# -1-_-01-00-001.net
KiCad netlist of a schematic drawn in Altium Designer
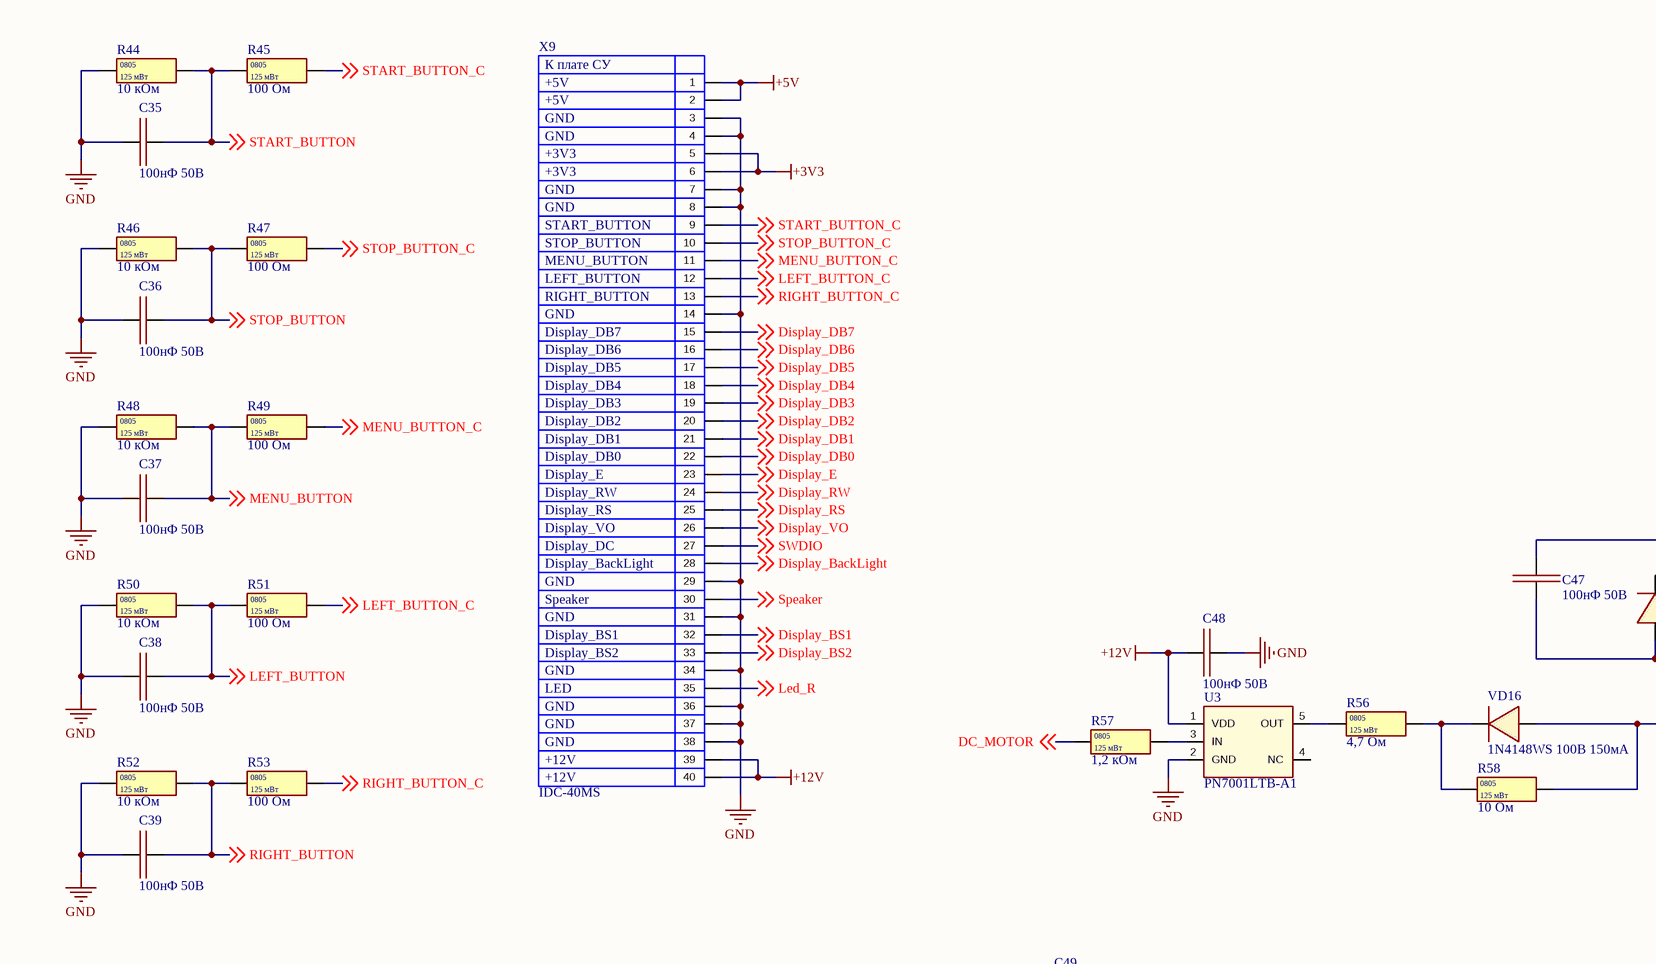
[diagram p0: СТЖ-1-ПУ-01-00-001.SchDoc, top left]
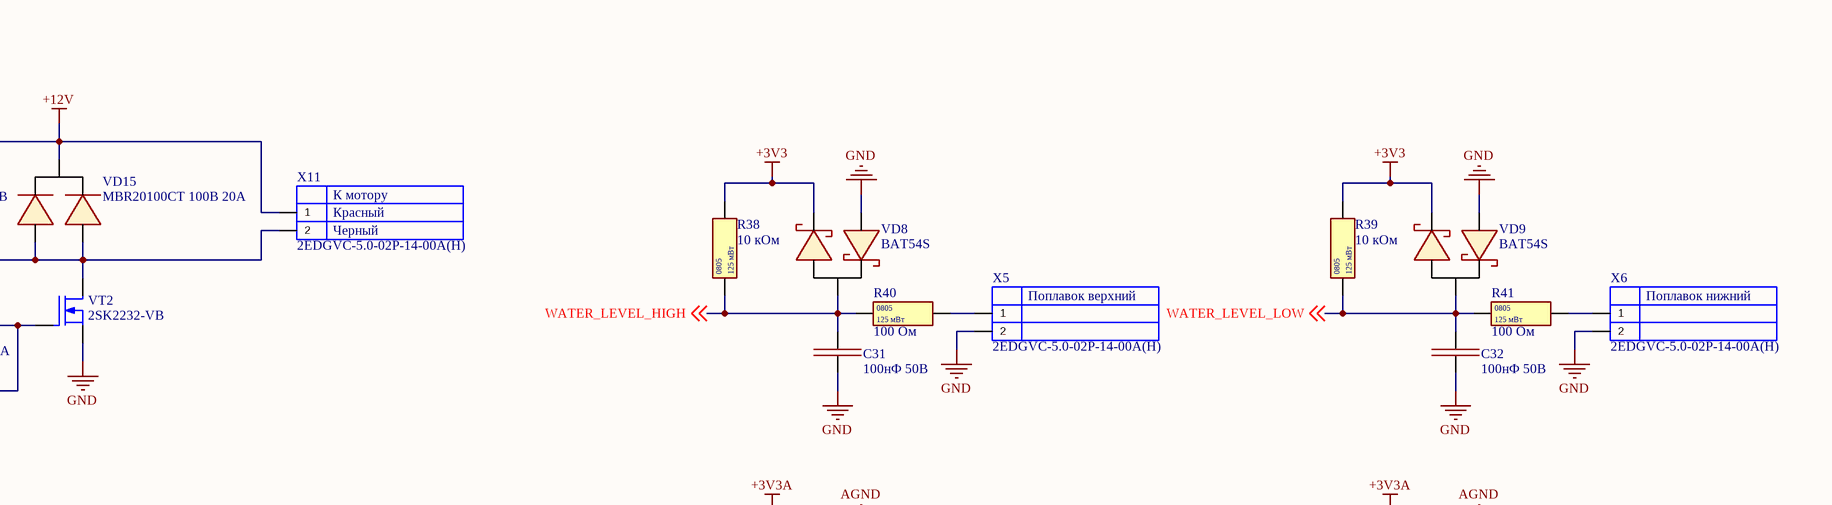
[diagram p1: СТЖ-1-ПУ-01-00-001.SchDoc, top right]
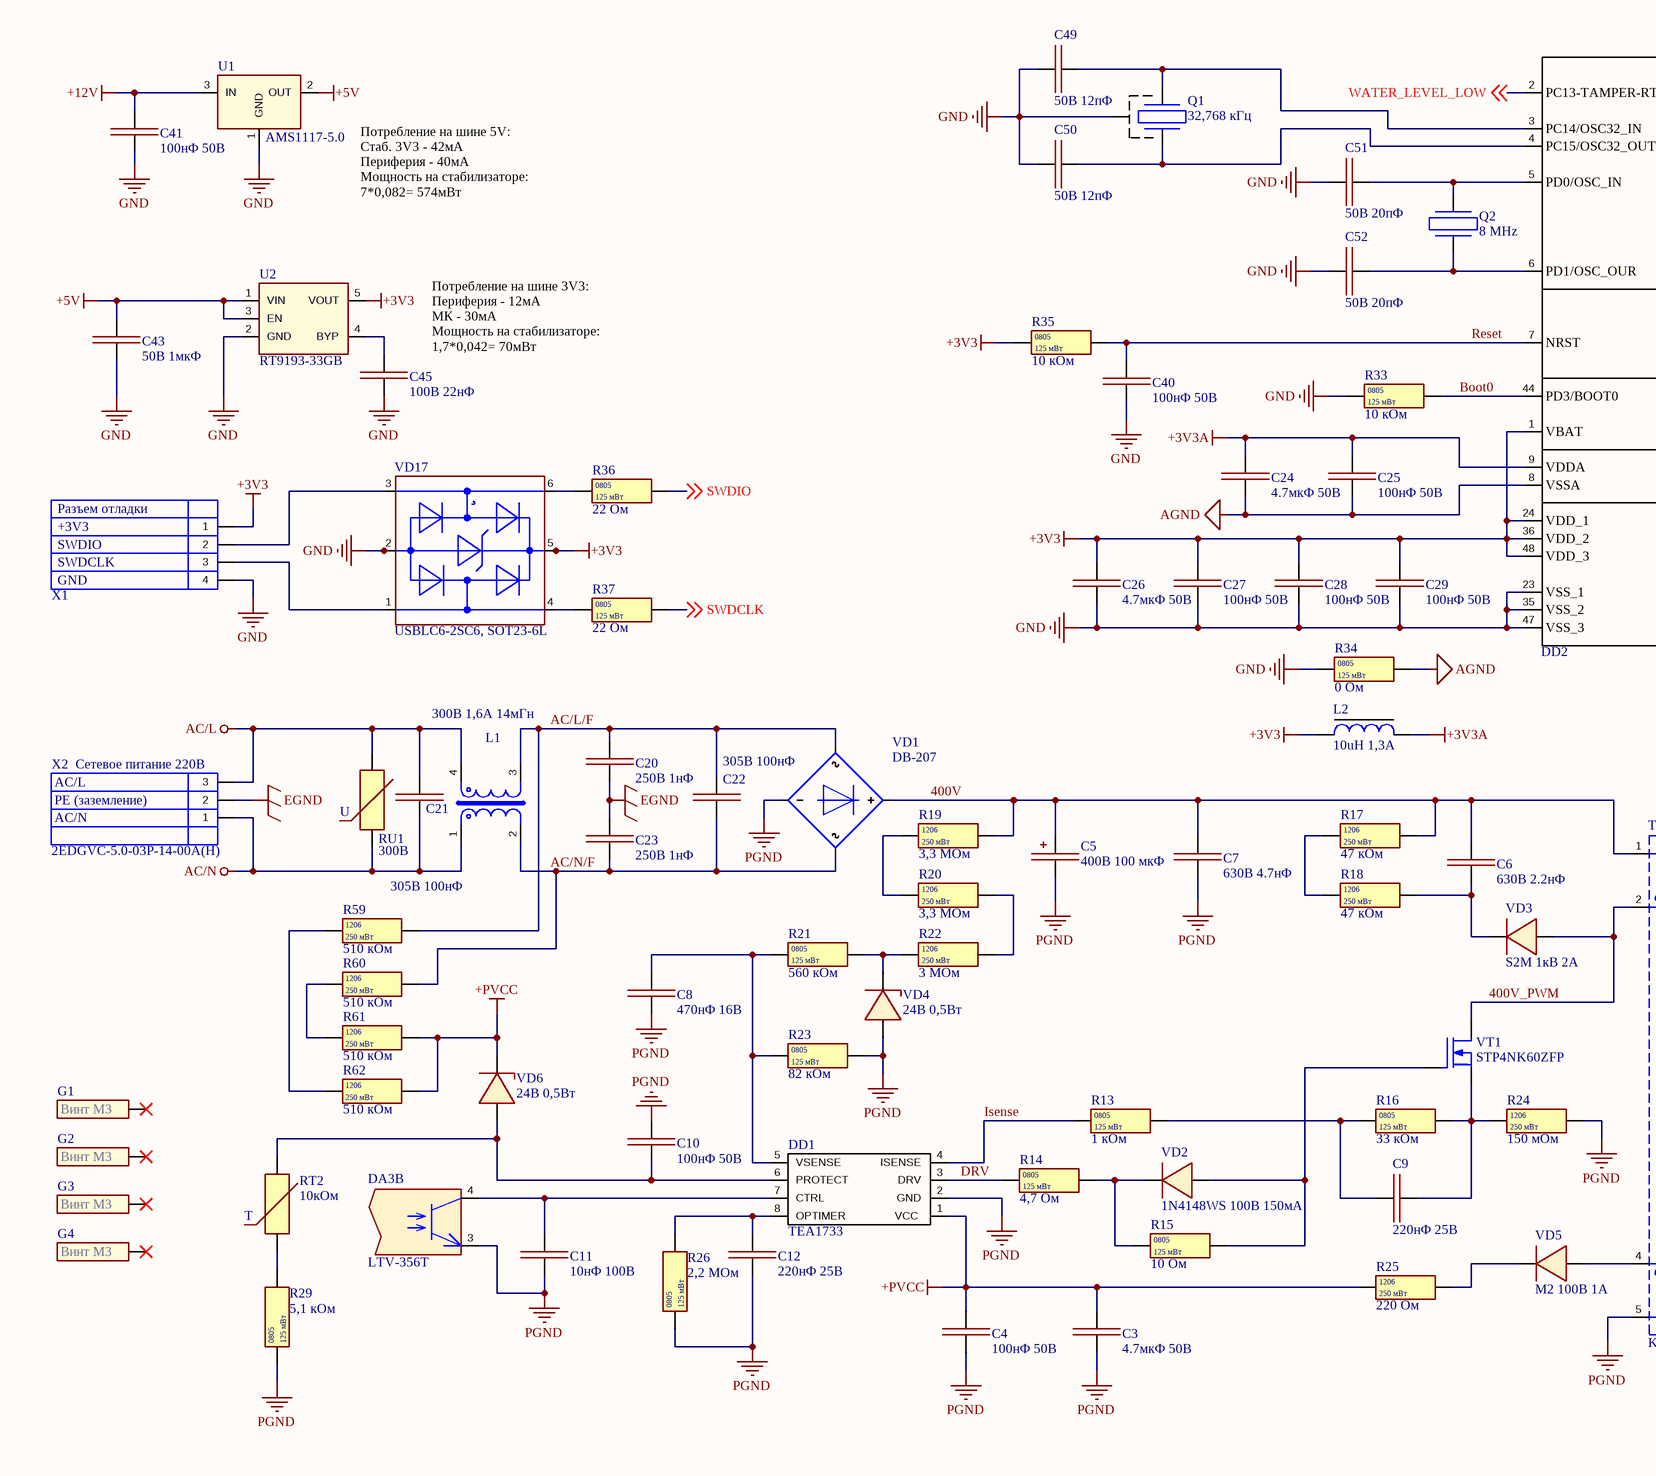
[diagram p2: СТЖ-1-ПУ-01-00-001.SchDoc, bottom left]
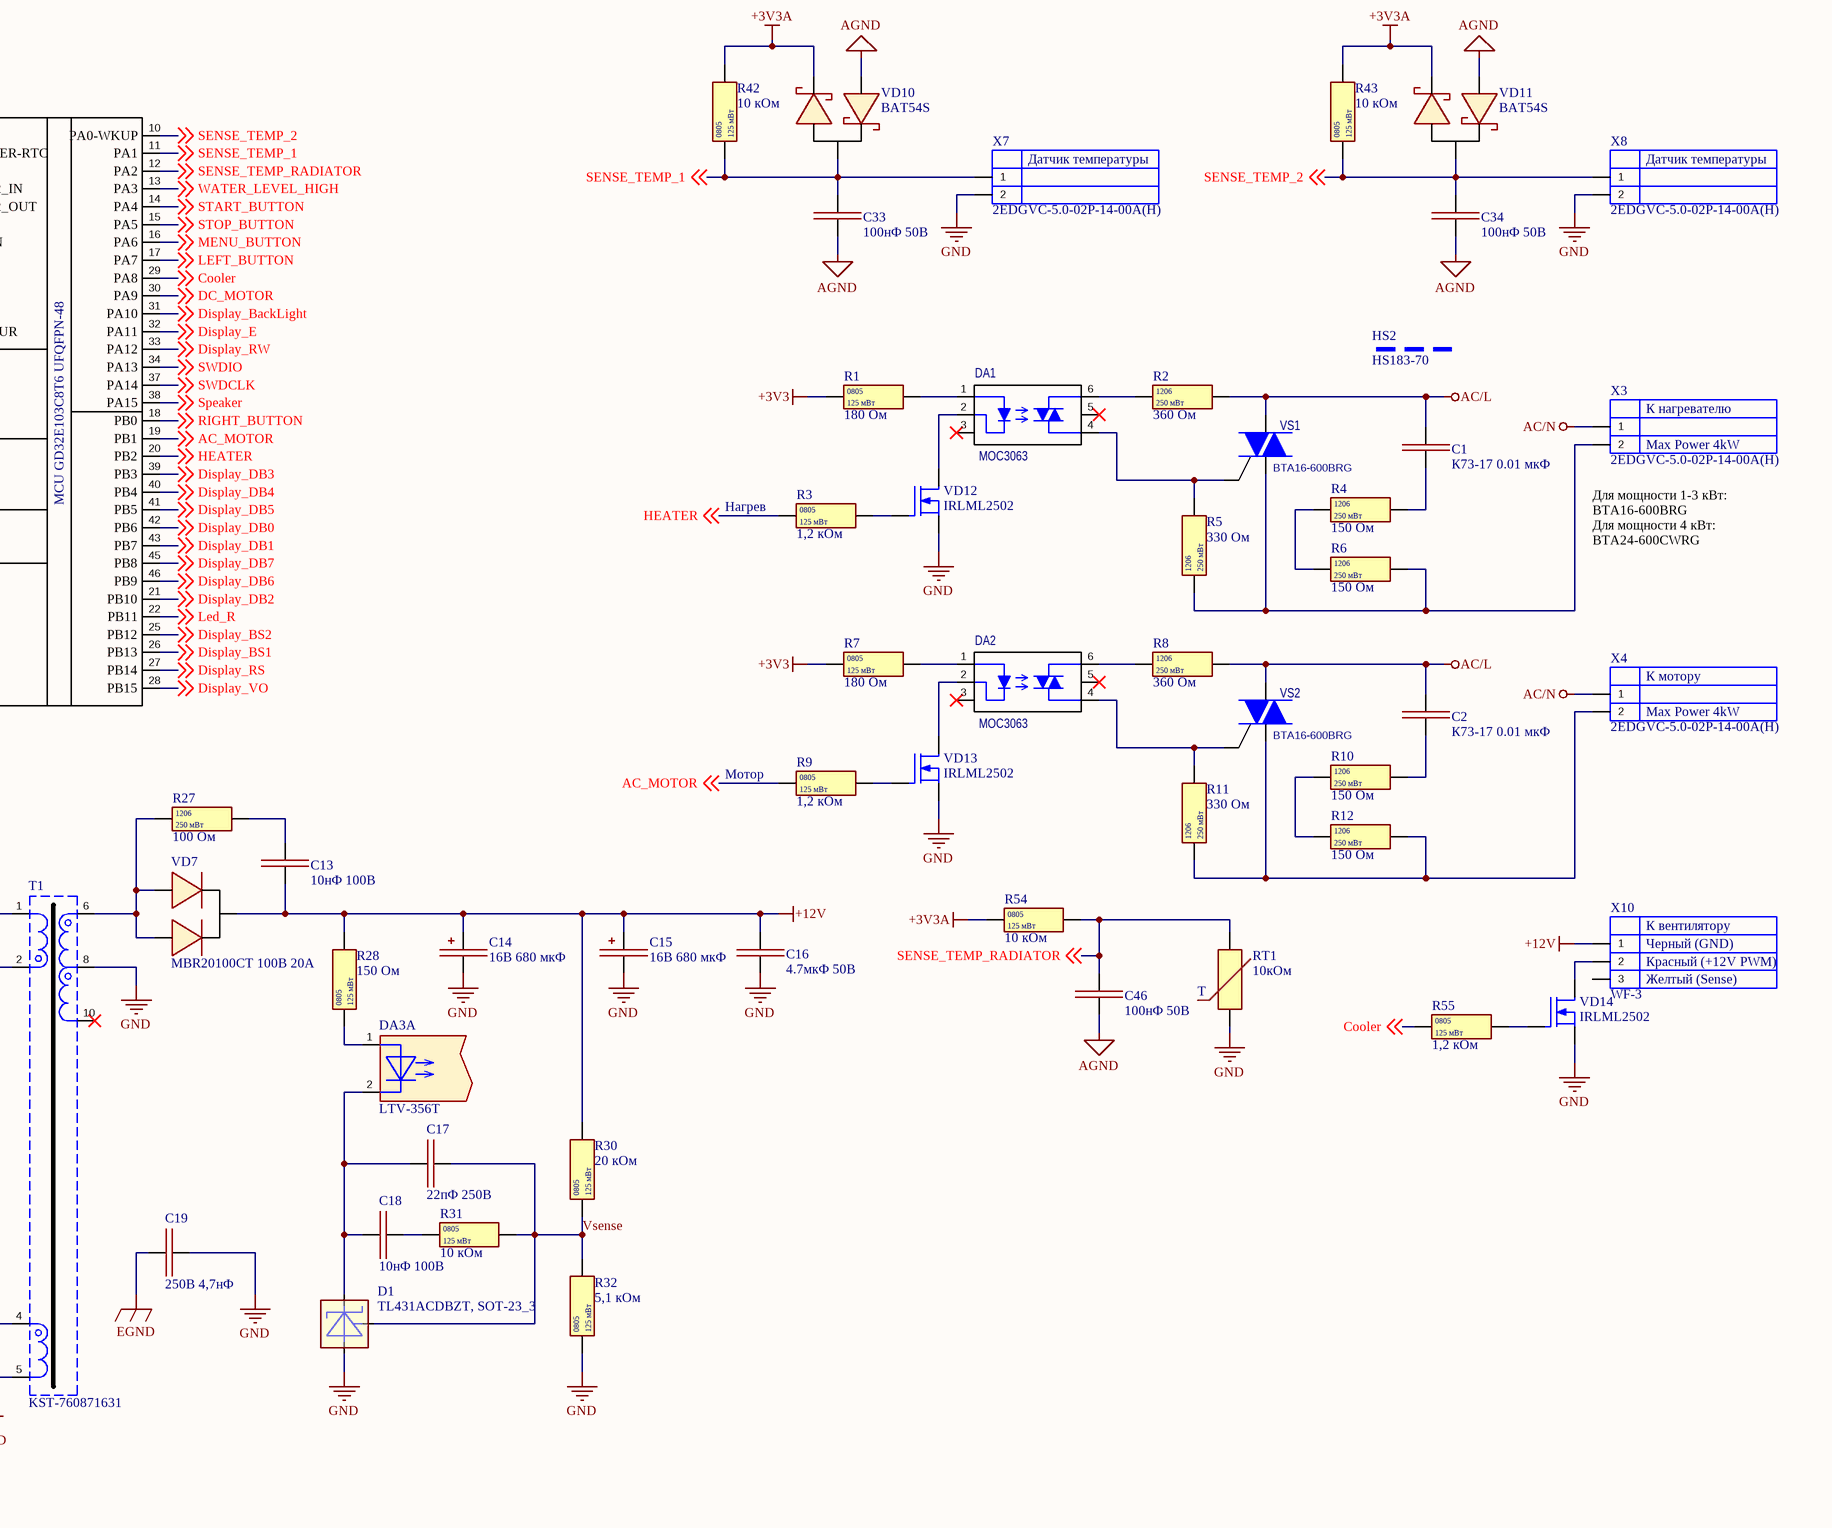
[diagram p3: СТЖ-1-ПУ-01-00-001.SchDoc, bottom right]

(export (version "E")
  (design (tool "Eeschema 10.0.6"))
  (components
    (comp (ref "C1")
      (value "К73-17 0.01 мкФ")
      (footprint "K73_17_400V")
      (description "Конденсатор К73-17 0.01 мкФ - 400 В - 10%")
      (libsource (lib "Schlib") (part "К73-17 0.01 мкФ - 400 В"))
    )
    (comp (ref "C2")
      (value "К73-17 0.01 мкФ")
      (footprint "K73_17_400V")
      (description "Конденсатор К73-17 0.01 мкФ - 400 В - 10%")
      (libsource (lib "Schlib") (part "К73-17 0.01 мкФ - 400 В"))
    )
    (comp (ref "C3")
      (value "4.7мкФ 50В")
      (footprint "C-1206")
      (description "Конденсатор 1206 10% 50В 4.7мкФ X7R")
      (libsource (lib "Schlib") (part "CC1206KKX7R9BB475"))
    )
    (comp (ref "C4")
      (value "100нФ 50В")
      (footprint "C-0805")
      (description "Конденсатор 0805 10% 50В 100нФ X7R")
      (libsource (lib "Schlib") (part "GRM21BR71H104KA01L"))
    )
    (comp (ref "C5")
      (value "400В 100 мкФ")
      (footprint "JNE_22x25")
      (description "Конденсатор Эл-лит. 20% 400В 100 мкФ")
      (libsource (lib "Schlib") (part "JNE2G101M10002200250"))
    )
    (comp (ref "C6")
      (value "630В 2.2нФ")
      (footprint "C-1206")
      (description "Конденсатор 1206 10% 630В 2.2нФ X7R")
      (libsource (lib "Schlib") (part "GRM31BR72J222KW01L"))
    )
    (comp (ref "C7")
      (value "630В 4.7нФ")
      (footprint "C-1206")
      (description "Конденсатор 1206 10% 630В 4.7нФ X7R")
      (libsource (lib "Schlib") (part "GRM31BR72J472KW01L"))
    )
    (comp (ref "C8")
      (value "470нФ 16В")
      (footprint "C-0805")
      (description "Конденсатор 0805 10% 16В 470нФ X7R")
      (libsource (lib "Schlib") (part "GRM219R71C474K"))
    )
    (comp (ref "C9")
      (value "220нФ 25В")
      (footprint "C-0805")
      (description "Конденсатор 0805 10% 25В 220нФ X7R")
      (libsource (lib "Schlib") (part "GRM219R71E224K"))
    )
    (comp (ref "C10")
      (value "100нФ 50В")
      (footprint "C-0805")
      (description "Конденсатор 0805 10% 50В 100нФ X7R")
      (libsource (lib "Schlib") (part "GRM21BR71H104KA01L"))
    )
    (comp (ref "C11")
      (value "10нФ 100В")
      (footprint "C-0805")
      (description "Конденсатор 0805 10% 100В 10нФ X7R")
      (libsource (lib "Schlib") (part "GRM21BR72A103KA01L"))
    )
    (comp (ref "C12")
      (value "220нФ 25В")
      (footprint "C-0805")
      (description "Конденсатор 0805 10% 25В 220нФ X7R")
      (libsource (lib "Schlib") (part "GRM219R71E224K"))
    )
    (comp (ref "C13")
      (value "10нФ 100В")
      (footprint "C-0805")
      (description "Конденсатор 0805 10% 100В 10нФ X7R")
      (libsource (lib "Schlib") (part "GRM21BR72A103KA01L"))
    )
    (comp (ref "C14")
      (value "16В 680 мкФ")
      (footprint "JRC_8x16")
      (description "Конденсатор Эл-лит. 20% 16В 680 мкФ")
      (libsource (lib "Schlib") (part "JRC1C681M03500800160000B"))
    )
    (comp (ref "C15")
      (value "16В 680 мкФ")
      (footprint "JRC_8x16")
      (description "Конденсатор Эл-лит. 20% 16В 680 мкФ")
      (libsource (lib "Schlib") (part "JRC1C681M03500800160000B"))
    )
    (comp (ref "C16")
      (value "4.7мкФ 50В")
      (footprint "C-1206")
      (description "Конденсатор 1206 10% 50В 4.7мкФ X7R")
      (libsource (lib "Schlib") (part "CC1206KKX7R9BB475"))
    )
    (comp (ref "C17")
      (value "22пФ 250В")
      (footprint "C-0805")
      (description "Конденсатор 0805 10% 250В 22пФ C0G")
      (libsource (lib "Schlib") (part "GRM21A5C2E220J"))
    )
    (comp (ref "C18")
      (value "10нФ 100В")
      (footprint "C-0805")
      (description "Конденсатор 0805 10% 100В 10нФ X7R")
      (libsource (lib "Schlib") (part "GRM21BR72A103KA01L"))
    )
    (comp (ref "C19")
      (value "250В 4,7нФ")
      (footprint "C_X/Y_10mm")
      (description "Конденсатор X1/Y1 20% 250В 4,7нФ")
      (libsource (lib "Schlib") (part "DE1E3KX472MN4AN01F"))
    )
    (comp (ref "C20")
      (value "250В 1нФ")
      (footprint "C_X/Y_10mm")
      (description "Конденсатор X1/Y1 20% 250В 1нФ")
      (libsource (lib "Schlib") (part "DE1E3KX102MA4BN01F"))
    )
    (comp (ref "C21")
      (value "305В 100нФ")
      (footprint "B32922_5x10.5x18")
      (description "Конденсатор X2 Пропилен 10% 305В 100нФ")
      (libsource (lib "Schlib") (part "B32922C3104K000"))
    )
    (comp (ref "C22")
      (value "305В 100нФ")
      (footprint "B32922_5x10.5x18")
      (description "Конденсатор X2 Пропилен 10% 305В 100нФ")
      (libsource (lib "Schlib") (part "B32922C3104K000"))
    )
    (comp (ref "C23")
      (value "250В 1нФ")
      (footprint "C_X/Y_10mm")
      (description "Конденсатор X1/Y1 20% 250В 1нФ")
      (libsource (lib "Schlib") (part "DE1E3KX102MA4BN01F"))
    )
    (comp (ref "C24")
      (value "4.7мкФ 50В")
      (footprint "C-1206")
      (description "Конденсатор 1206 10% 50В 4.7мкФ X7R")
      (libsource (lib "Schlib") (part "CC1206KKX7R9BB475"))
    )
    (comp (ref "C25")
      (value "100нФ 50В")
      (footprint "C-0805")
      (description "Конденсатор 0805 10% 50В 100нФ X7R")
      (libsource (lib "Schlib") (part "GRM21BR71H104KA01L"))
    )
    (comp (ref "C26")
      (value "4.7мкФ 50В")
      (footprint "C-1206")
      (description "Конденсатор 1206 10% 50В 4.7мкФ X7R")
      (libsource (lib "Schlib") (part "CC1206KKX7R9BB475"))
    )
    (comp (ref "C27")
      (value "100нФ 50В")
      (footprint "C-0805")
      (description "Конденсатор 0805 10% 50В 100нФ X7R")
      (libsource (lib "Schlib") (part "GRM21BR71H104KA01L"))
    )
    (comp (ref "C28")
      (value "100нФ 50В")
      (footprint "C-0805")
      (description "Конденсатор 0805 10% 50В 100нФ X7R")
      (libsource (lib "Schlib") (part "GRM21BR71H104KA01L"))
    )
    (comp (ref "C29")
      (value "100нФ 50В")
      (footprint "C-0805")
      (description "Конденсатор 0805 10% 50В 100нФ X7R")
      (libsource (lib "Schlib") (part "GRM21BR71H104KA01L"))
    )
    (comp (ref "C31")
      (value "100нФ 50В")
      (footprint "C-0805")
      (description "Конденсатор 0805 10% 50В 100нФ X7R")
      (libsource (lib "Schlib") (part "GRM21BR71H104KA01L"))
    )
    (comp (ref "C32")
      (value "100нФ 50В")
      (footprint "C-0805")
      (description "Конденсатор 0805 10% 50В 100нФ X7R")
      (libsource (lib "Schlib") (part "GRM21BR71H104KA01L"))
    )
    (comp (ref "C33")
      (value "100нФ 50В")
      (footprint "C-0805")
      (description "Конденсатор 0805 10% 50В 100нФ X7R")
      (libsource (lib "Schlib") (part "GRM21BR71H104KA01L"))
    )
    (comp (ref "C34")
      (value "100нФ 50В")
      (footprint "C-0805")
      (description "Конденсатор 0805 10% 50В 100нФ X7R")
      (libsource (lib "Schlib") (part "GRM21BR71H104KA01L"))
    )
    (comp (ref "C35")
      (value "100нФ 50В")
      (footprint "C-0805")
      (description "Конденсатор 0805 10% 50В 100нФ X7R")
      (libsource (lib "Schlib") (part "GRM21BR71H104KA01L"))
    )
    (comp (ref "C36")
      (value "100нФ 50В")
      (footprint "C-0805")
      (description "Конденсатор 0805 10% 50В 100нФ X7R")
      (libsource (lib "Schlib") (part "GRM21BR71H104KA01L"))
    )
    (comp (ref "C37")
      (value "100нФ 50В")
      (footprint "C-0805")
      (description "Конденсатор 0805 10% 50В 100нФ X7R")
      (libsource (lib "Schlib") (part "GRM21BR71H104KA01L"))
    )
    (comp (ref "C38")
      (value "100нФ 50В")
      (footprint "C-0805")
      (description "Конденсатор 0805 10% 50В 100нФ X7R")
      (libsource (lib "Schlib") (part "GRM21BR71H104KA01L"))
    )
    (comp (ref "C39")
      (value "100нФ 50В")
      (footprint "C-0805")
      (description "Конденсатор 0805 10% 50В 100нФ X7R")
      (libsource (lib "Schlib") (part "GRM21BR71H104KA01L"))
    )
    (comp (ref "C40")
      (value "100нФ 50В")
      (footprint "C-0805")
      (description "Конденсатор 0805 10% 50В 100нФ X7R")
      (libsource (lib "Schlib") (part "GRM21BR71H104KA01L"))
    )
    (comp (ref "C41")
      (value "100нФ 50В")
      (footprint "C-0805")
      (description "Конденсатор 0805 10% 50В 100нФ X7R")
      (libsource (lib "Schlib") (part "GRM21BR71H104KA01L"))
    )
    (comp (ref "C43")
      (value "50В 1мкФ")
      (footprint "C-0805-1.25h")
      (description "Конденсатор 0805 10% 50В 1мкФ X7R")
      (libsource (lib "Schlib") (part "GRM21BR71H105KA12L"))
    )
    (comp (ref "C45")
      (value "100В 22нФ")
      (footprint "C-0805-1.25h")
      (description "Конденсатор 0805 10% 100В 22нФ X7R")
      (libsource (lib "Schlib") (part "GRM21BR72A223KA01L"))
    )
    (comp (ref "C46")
      (value "100нФ 50В")
      (footprint "C-0805")
      (description "Конденсатор 0805 10% 50В 100нФ X7R")
      (libsource (lib "Schlib") (part "GRM21BR71H104KA01L"))
    )
    (comp (ref "C47")
      (value "100нФ 50В")
      (footprint "C-0805")
      (description "Конденсатор 0805 10% 50В 100нФ X7R")
      (libsource (lib "Schlib") (part "GRM21BR71H104KA01L"))
    )
    (comp (ref "C48")
      (value "100нФ 50В")
      (footprint "C-0805")
      (description "Конденсатор 0805 10% 50В 100нФ X7R")
      (libsource (lib "Schlib") (part "GRM21BR71H104KA01L"))
    )
    (comp (ref "C49")
      (value "50В 12пФ")
      (footprint "C-0603-0.9h")
      (description "Конденсатор 0603 05% 50В 12пФ NP0")
      (libsource (lib "Schlib") (part "CC0603JRNPO9BN120"))
    )
    (comp (ref "C50")
      (value "50В 12пФ")
      (footprint "C-0603-0.9h")
      (description "Конденсатор 0603 05% 50В 12пФ NP0")
      (libsource (lib "Schlib") (part "CC0603JRNPO9BN120"))
    )
    (comp (ref "C51")
      (value "50В 20пФ")
      (footprint "C-0805-1.25h")
      (description "Конденсатор 0805 05% 50В 20пФ NP0")
      (libsource (lib "Schlib") (part "CC0805JRNPO9BN200"))
    )
    (comp (ref "C52")
      (value "50В 20пФ")
      (footprint "C-0805-1.25h")
      (description "Конденсатор 0805 05% 50В 20пФ NP0")
      (libsource (lib "Schlib") (part "CC0805JRNPO9BN200"))
    )
    (comp (ref "D1")
      (value "TL431ACDBZT, SOT-23_3")
      (footprint "SOT-23_BEC")
      (description "ИОН TL431ACDBZT, SOT-23_3")
      (fields
        (field (name "COMPONENTLINK1URL") "D:\\ММЦМ.303359 - Система разгрузки\\#Приложение\\BC847_SER.pdf")
      )
      (libsource (lib "Schlib") (part "TL431ACDBZT, SOT-23_3"))
    )
    (comp (ref "DA1")
      (value "MOC3063")
      (footprint "DIP6")
      (description "Оптосимистор MOC3063, DIP6 zero-cross")
      (libsource (lib "Schlib") (part "MOC3063"))
    )
    (comp (ref "DA2")
      (value "MOC3063")
      (footprint "DIP6")
      (description "Оптосимистор MOC3063, DIP6 zero-cross")
      (libsource (lib "Schlib") (part "MOC3063"))
    )
    (comp (ref "DA3")
      (value "LTV-356T")
      (footprint "PC817 - DIP4")
      (description "Оптрон PC817, DIP-4")
      (libsource (lib "Schlib") (part "LTV-356T"))
    )
    (comp (ref "DD1")
      (value "TEA1733")
      (footprint "SOIC-8")
      (description "AC/DC TEA1733, SO8")
      (libsource (lib "Schlib") (part "TEA1733"))
    )
    (comp (ref "DD2")
      (value "MCU GD32E103C8T6 UFQFPN-48")
      (footprint "LQFP48")
      (description "Микроконтроллер")
      (libsource (lib "Schlib") (part "GD32E103C8T6"))
    )
    (comp (ref "G1")
      (value "Винт М3")
      (footprint "Standoff M3")
      (description "Винт М3 DIN 967")
      (libsource (lib "Schlib") (part "Винт М3"))
    )
    (comp (ref "G2")
      (value "Винт М3")
      (footprint "Standoff M3")
      (description "Винт М3 DIN 967")
      (libsource (lib "Schlib") (part "Винт М3"))
    )
    (comp (ref "G3")
      (value "Винт М3")
      (footprint "Standoff M3")
      (description "Винт М3 DIN 967")
      (libsource (lib "Schlib") (part "Винт М3"))
    )
    (comp (ref "G4")
      (value "Винт М3")
      (footprint "Standoff M3")
      (description "Винт М3 DIN 967")
      (libsource (lib "Schlib") (part "Винт М3"))
    )
    (comp (ref "HS2")
      (value "HS183-70")
      (footprint "HS183-70")
      (description "Радиатор HS183-70")
      (libsource (lib "Schlib") (part "HS183-70"))
    )
    (comp (ref "L1")
      (value "300В 1,6А 14мГн")
      (footprint "MURATA_PLY_STANDART")
      (description "Фильтр ЭМП 300В 1,6А 14мГн")
      (libsource (lib "Schlib") (part "PLY10AN1521R6R2"))
    )
    (comp (ref "L2")
      (value "10uH 1,3A")
      (footprint "CD54")
      (description "Дроссель 10% 10uH 1,3A")
      (libsource (lib "Schlib") (part "CD54-100K"))
    )
    (comp (ref "Q1")
      (value "32,768 кГц")
      (footprint "DT-26")
      (description "Кварцевый резонатор 32,768 кГц")
      (libsource (lib "Schlib") (part "DT-26"))
    )
    (comp (ref "Q2")
      (value "8 MHz")
      (footprint "HC-49U")
      (description "Кварцевый резонатор 8MHz HC49")
      (libsource (lib "Schlib") (part "L-KLS14-HC-49S-8.000-20-30-A"))
    )
    (comp (ref "R1")
      (value "180 Ом")
      (footprint "R-0805")
      (description "Резистор 0805 5% 180 Ом")
      (libsource (lib "Schlib") (part "RC0805JR-07180RL"))
    )
    (comp (ref "R2")
      (value "360 Ом")
      (footprint "R-1206")
      (description "Резистор 1206 5% 360 Ом")
      (libsource (lib "Schlib") (part "RC1206JR-07360RL"))
    )
    (comp (ref "R3")
      (value "1,2 кОм")
      (footprint "R-0805")
      (description "Резистор 0805 5% 1,2 кОм")
      (libsource (lib "Schlib") (part "RC0805JR-071K2L"))
    )
    (comp (ref "R4")
      (value "150 Ом")
      (footprint "R-1206")
      (description "Резистор 1206 5% 150 Ом")
      (libsource (lib "Schlib") (part "RC1206JR-07150RL"))
    )
    (comp (ref "R5")
      (value "330 Ом")
      (footprint "R-1206")
      (description "Резистор 1206 5% 330 Ом")
      (libsource (lib "Schlib") (part "RC1206JR-07330RL"))
    )
    (comp (ref "R6")
      (value "150 Ом")
      (footprint "R-1206")
      (description "Резистор 1206 5% 150 Ом")
      (libsource (lib "Schlib") (part "RC1206JR-07150RL"))
    )
    (comp (ref "R7")
      (value "180 Ом")
      (footprint "R-0805")
      (description "Резистор 0805 5% 180 Ом")
      (libsource (lib "Schlib") (part "RC0805JR-07180RL"))
    )
    (comp (ref "R8")
      (value "360 Ом")
      (footprint "R-1206")
      (description "Резистор 1206 5% 360 Ом")
      (libsource (lib "Schlib") (part "RC1206JR-07360RL"))
    )
    (comp (ref "R9")
      (value "1,2 кОм")
      (footprint "R-0805")
      (description "Резистор 0805 5% 1,2 кОм")
      (libsource (lib "Schlib") (part "RC0805JR-071K2L"))
    )
    (comp (ref "R10")
      (value "150 Ом")
      (footprint "R-1206")
      (description "Резистор 1206 5% 150 Ом")
      (libsource (lib "Schlib") (part "RC1206JR-07150RL"))
    )
    (comp (ref "R11")
      (value "330 Ом")
      (footprint "R-1206")
      (description "Резистор 1206 5% 330 Ом")
      (libsource (lib "Schlib") (part "RC1206JR-07330RL"))
    )
    (comp (ref "R12")
      (value "150 Ом")
      (footprint "R-1206")
      (description "Резистор 1206 5% 150 Ом")
      (libsource (lib "Schlib") (part "RC1206JR-07150RL"))
    )
    (comp (ref "R13")
      (value "1 кОм")
      (footprint "R-0805")
      (description "Резистор 0805 5% 1 кОм")
      (libsource (lib "Schlib") (part "RC0805JR-071KL"))
    )
    (comp (ref "R14")
      (value "4,7 Ом")
      (footprint "R-0805")
      (description "Резистор 0805 5% 4,7 Ом")
      (libsource (lib "Schlib") (part "RC0805JR-074R7L"))
    )
    (comp (ref "R15")
      (value "10 Ом")
      (footprint "R-0805")
      (description "Резистор 0805 5% 10 Ом")
      (libsource (lib "Schlib") (part "RC0805JR-0710RL"))
    )
    (comp (ref "R16")
      (value "33 кОм")
      (footprint "R-0805")
      (description "Резистор 0805 5% 33 кОм")
      (libsource (lib "Schlib") (part "RC0805JR-0733KL"))
    )
    (comp (ref "R17")
      (value "47 кОм")
      (footprint "R-1206")
      (description "Резистор 1206 5% 47 кОм")
      (libsource (lib "Schlib") (part "RC1206JR-0747КL"))
    )
    (comp (ref "R18")
      (value "47 кОм")
      (footprint "R-1206")
      (description "Резистор 1206 5% 47 кОм")
      (libsource (lib "Schlib") (part "RC1206JR-0747КL"))
    )
    (comp (ref "R19")
      (value "3,3 МОм")
      (footprint "R-1206")
      (description "Резистор 1206 5% 3,3 МОм")
      (libsource (lib "Schlib") (part "RC1206JR-073M3L"))
    )
    (comp (ref "R20")
      (value "3,3 МОм")
      (footprint "R-1206")
      (description "Резистор 1206 5% 3,3 МОм")
      (libsource (lib "Schlib") (part "RC1206JR-073M3L"))
    )
    (comp (ref "R21")
      (value "560 кОм")
      (footprint "R-0805")
      (description "Резистор 0805 5% 560 кОм")
      (libsource (lib "Schlib") (part "RC0805JR-07560KL"))
    )
    (comp (ref "R22")
      (value "3 МОм")
      (footprint "R-1206")
      (description "Резистор 1206 5% 3 МОм")
      (libsource (lib "Schlib") (part "RC1206JR-073ML"))
    )
    (comp (ref "R23")
      (value "82 кОм")
      (footprint "R-0805")
      (description "Резистор 0805 5% 82 кОм")
      (libsource (lib "Schlib") (part "RC0805JR-0782KL"))
    )
    (comp (ref "R24")
      (value "150 мОм")
      (footprint "R-1206")
      (description "Резистор 1206 1% 150 мОм импульсный")
      (libsource (lib "Schlib") (part "ERJ8BSFR15V"))
    )
    (comp (ref "R25")
      (value "220 Ом")
      (footprint "R-1206")
      (description "Резистор 1206 1% 220 Ом")
      (libsource (lib "Schlib") (part "RC1206FR-07220RL"))
    )
    (comp (ref "R26")
      (value "2,2 МОм")
      (footprint "R-0805")
      (description "Резистор 0805 5% 2,2 МОм")
      (libsource (lib "Schlib") (part "RC0805JR-072M2L"))
    )
    (comp (ref "R27")
      (value "100 Ом")
      (footprint "R-1206")
      (description "Резистор 1206 5% 100 Ом")
      (libsource (lib "Schlib") (part "RC1206JR-07100RL"))
    )
    (comp (ref "R28")
      (value "150 Ом")
      (footprint "R-0805")
      (description "Резистор 0805 5% 150 Ом")
      (libsource (lib "Schlib") (part "RC0805JR-07150KL"))
    )
    (comp (ref "R29")
      (value "5,1 кОм")
      (footprint "R-0805")
      (description "Резистор 0805 5% 5,1 кОм")
      (libsource (lib "Schlib") (part "RC0805JR-075K1L"))
    )
    (comp (ref "R30")
      (value "20 кОм")
      (footprint "R-0805")
      (description "Резистор 0805 1% 20 кОм")
      (libsource (lib "Schlib") (part "RC0805FR-0720KL"))
    )
    (comp (ref "R31")
      (value "10 кОм")
      (footprint "R-0805")
      (description "Резистор 0805 5% 10 кОм")
      (libsource (lib "") (part "RC0805JR-0710KL_1"))
    )
    (comp (ref "R32")
      (value "5,1 кОм")
      (footprint "R-0805")
      (description "Резистор 0805 1% 5,1 кОм")
      (libsource (lib "Schlib") (part "RC0805FR-075K1L"))
    )
    (comp (ref "R33")
      (value "10 кОм")
      (footprint "R-0805")
      (description "Резистор 0805 5% 10 кОм")
      (libsource (lib "") (part "RC0805JR-0710KL_1"))
    )
    (comp (ref "R34")
      (value "0 Ом")
      (footprint "R-0805")
      (description "Резистор 0805 5% 0 Ом")
      (libsource (lib "Schlib") (part "RC0805JR-070RL"))
    )
    (comp (ref "R35")
      (value "10 кОм")
      (footprint "R-0805")
      (description "Резистор 0805 5% 10 кОм")
      (libsource (lib "") (part "RC0805JR-0710KL_1"))
    )
    (comp (ref "R36")
      (value "22 Ом")
      (footprint "R-0805")
      (description "Резистор 0805 5% 22 Ом")
      (libsource (lib "Schlib") (part "RC0805JR-0722RL"))
    )
    (comp (ref "R37")
      (value "22 Ом")
      (footprint "R-0805")
      (description "Резистор 0805 5% 22 Ом")
      (libsource (lib "Schlib") (part "RC0805JR-0722RL"))
    )
    (comp (ref "R38")
      (value "10 кОм")
      (footprint "R-0805")
      (description "Резистор 0805 5% 10 кОм")
      (libsource (lib "Schlib") (part "RC0805JR-0710KL"))
    )
    (comp (ref "R39")
      (value "10 кОм")
      (footprint "R-0805")
      (description "Резистор 0805 5% 10 кОм")
      (libsource (lib "Schlib") (part "RC0805JR-0710KL"))
    )
    (comp (ref "R40")
      (value "100 Ом")
      (footprint "R-0805")
      (description "Резистор 0805 5% 100 Ом")
      (libsource (lib "Schlib") (part "RC0805JR-07100RL"))
    )
    (comp (ref "R41")
      (value "100 Ом")
      (footprint "R-0805")
      (description "Резистор 0805 5% 100 Ом")
      (libsource (lib "Schlib") (part "RC0805JR-07100RL"))
    )
    (comp (ref "R42")
      (value "10 кОм")
      (footprint "R-0805")
      (description "Резистор 0805 5% 10 кОм")
      (libsource (lib "Schlib") (part "RC0805JR-0710KL"))
    )
    (comp (ref "R43")
      (value "10 кОм")
      (footprint "R-0805")
      (description "Резистор 0805 5% 10 кОм")
      (libsource (lib "Schlib") (part "RC0805JR-0710KL"))
    )
    (comp (ref "R44")
      (value "10 кОм")
      (footprint "R-0805")
      (description "Резистор 0805 5% 10 кОм")
      (libsource (lib "") (part "RC0805JR-0710KL_1"))
    )
    (comp (ref "R45")
      (value "100 Ом")
      (footprint "R-0805")
      (description "Резистор 0805 5% 100 Ом")
      (libsource (lib "Schlib") (part "RC0805JR-07100RL"))
    )
    (comp (ref "R46")
      (value "10 кОм")
      (footprint "R-0805")
      (description "Резистор 0805 5% 10 кОм")
      (libsource (lib "") (part "RC0805JR-0710KL_1"))
    )
    (comp (ref "R47")
      (value "100 Ом")
      (footprint "R-0805")
      (description "Резистор 0805 5% 100 Ом")
      (libsource (lib "Schlib") (part "RC0805JR-07100RL"))
    )
    (comp (ref "R48")
      (value "10 кОм")
      (footprint "R-0805")
      (description "Резистор 0805 5% 10 кОм")
      (libsource (lib "") (part "RC0805JR-0710KL_1"))
    )
    (comp (ref "R49")
      (value "100 Ом")
      (footprint "R-0805")
      (description "Резистор 0805 5% 100 Ом")
      (libsource (lib "Schlib") (part "RC0805JR-07100RL"))
    )
    (comp (ref "R50")
      (value "10 кОм")
      (footprint "R-0805")
      (description "Резистор 0805 5% 10 кОм")
      (libsource (lib "") (part "RC0805JR-0710KL_1"))
    )
    (comp (ref "R51")
      (value "100 Ом")
      (footprint "R-0805")
      (description "Резистор 0805 5% 100 Ом")
      (libsource (lib "Schlib") (part "RC0805JR-07100RL"))
    )
    (comp (ref "R52")
      (value "10 кОм")
      (footprint "R-0805")
      (description "Резистор 0805 5% 10 кОм")
      (libsource (lib "") (part "RC0805JR-0710KL_1"))
    )
    (comp (ref "R53")
      (value "100 Ом")
      (footprint "R-0805")
      (description "Резистор 0805 5% 100 Ом")
      (libsource (lib "Schlib") (part "RC0805JR-07100RL"))
    )
    (comp (ref "R54")
      (value "10 кОм")
      (footprint "R-0805")
      (description "Резистор 0805 5% 10 кОм")
      (libsource (lib "") (part "RC0805JR-0710KL_1"))
    )
    (comp (ref "R55")
      (value "1,2 кОм")
      (footprint "R-0805")
      (description "Резистор 0805 5% 1,2 кОм")
      (libsource (lib "Schlib") (part "RC0805JR-071K2L"))
    )
    (comp (ref "R56")
      (value "4,7 Ом")
      (footprint "R-0805")
      (description "Резистор 0805 5% 4,7 Ом")
      (libsource (lib "Schlib") (part "RC0805JR-074R7L"))
    )
    (comp (ref "R57")
      (value "1,2 кОм")
      (footprint "R-0805")
      (description "Резистор 0805 5% 1,2 кОм")
      (libsource (lib "Schlib") (part "RC0805JR-071K2L"))
    )
    (comp (ref "R58")
      (value "10 Ом")
      (footprint "R-0805")
      (description "Резистор 0805 5% 10 Ом")
      (libsource (lib "Schlib") (part "RC0805JR-0710RL"))
    )
    (comp (ref "R59")
      (value "510 кОм")
      (footprint "R-1206")
      (description "Резистор 1206 5% 510 кОм")
      (libsource (lib "Schlib") (part "RC1206JR-07510KL"))
    )
    (comp (ref "R60")
      (value "510 кОм")
      (footprint "R-1206")
      (description "Резистор 1206 5% 510 кОм")
      (libsource (lib "Schlib") (part "RC1206JR-07510KL"))
    )
    (comp (ref "R61")
      (value "510 кОм")
      (footprint "R-1206")
      (description "Резистор 1206 5% 510 кОм")
      (libsource (lib "Schlib") (part "RC1206JR-07510KL"))
    )
    (comp (ref "R62")
      (value "510 кОм")
      (footprint "R-1206")
      (description "Резистор 1206 5% 510 кОм")
      (libsource (lib "Schlib") (part "RC1206JR-07510KL"))
    )
    (comp (ref "RT1")
      (value "10кОм")
      (footprint "Термистор 10k")
      (description "Термистор 1% 10кОм")
      (libsource (lib "Schlib") (part "B57861-S 103-F40"))
    )
    (comp (ref "RT2")
      (value "10кОм")
      (footprint "Термистор 10k")
      (description "Термистор 1% 10кОм")
      (libsource (lib "Schlib") (part "B57861-S 103-F40"))
    )
    (comp (ref "RU1")
      (value "300В")
      (footprint "U_7,5mm")
      (description "Варистор 10% 300В 300пФ 50А")
      (libsource (lib "Schlib") (part "B72214S0301K101"))
    )
    (comp (ref "T1")
      (value "KST-760871631")
      (footprint "KST-760871631")
      (description "Трансформатор KST-760871631")
      (libsource (lib "Schlib") (part "KST-760871631"))
    )
    (comp (ref "U1")
      (value "AMS1117-5.0")
      (footprint "SOT-223")
      (description "Лин. Стаб. 5V 800mA")
      (libsource (lib "Schlib") (part "AMS1117-5.0"))
    )
    (comp (ref "U2")
      (value "RT9193-33GB")
      (footprint "SOT23-5")
      (description "Лин. Стаб. 3.3V 300mA")
      (libsource (lib "Schlib") (part "RT9193-33GB"))
    )
    (comp (ref "U3")
      (value "PN7001LTB-A1")
      (footprint "SOT23-5")
      (description "Драйвер MOSFET 25V 3.5A")
      (libsource (lib "Schlib") (part "PN7001LTB-A1"))
    )
    (comp (ref "VD1")
      (value "DB-207")
      (footprint "DF-M")
      (description "Диодный мост DB-207")
      (libsource (lib "Schlib") (part "DB-207"))
    )
    (comp (ref "VD2")
      (value "1N4148WS 100В 150мА")
      (footprint "SOD-323")
      (description "Диод SOD-323 100В 150мА")
      (libsource (lib "Schlib") (part "1N4148WS"))
    )
    (comp (ref "VD3")
      (value "S2M 1кВ 2А")
      (footprint "SMB_2")
      (description "Диод SMA 1кВ 2А")
      (libsource (lib "Schlib") (part "S2M"))
    )
    (comp (ref "VD4")
      (value "24В 0,5Вт")
      (footprint "PcbLib:MINIMELF")
      (description "Стабилитрон miniMELF 24В 0,5Вт")
      (libsource (lib "Schlib") (part "BZV55C24"))
    )
    (comp (ref "VD5")
      (value "M2 100В 1А")
      (footprint "SMA")
      (description "Диод SMA 100В 1А")
      (libsource (lib "Schlib") (part "M2"))
    )
    (comp (ref "VD6")
      (value "24В 0,5Вт")
      (footprint "PcbLib:MINIMELF")
      (description "Стабилитрон miniMELF 24В 0,5Вт")
      (libsource (lib "Schlib") (part "BZV55C24"))
    )
    (comp (ref "VD7")
      (value "MBR20100CT 100В 20А")
      (footprint "TO220-3 bent")
      (description "Диод TO220 100В 20А")
      (libsource (lib "Schlib") (part "MBR20100CT"))
    )
    (comp (ref "VD8")
      (value "BAT54S")
      (footprint "SOT-23-3")
      (description "Диод BAT54S")
      (libsource (lib "Schlib") (part "BAT54S"))
    )
    (comp (ref "VD9")
      (value "BAT54S")
      (footprint "SOT-23-3")
      (description "Диод BAT54S")
      (libsource (lib "Schlib") (part "BAT54S"))
    )
    (comp (ref "VD10")
      (value "BAT54S")
      (footprint "SOT-23-3")
      (description "Диод BAT54S")
      (libsource (lib "Schlib") (part "BAT54S"))
    )
    (comp (ref "VD11")
      (value "BAT54S")
      (footprint "SOT-23-3")
      (description "Диод BAT54S")
      (libsource (lib "Schlib") (part "BAT54S"))
    )
    (comp (ref "VD12")
      (value "IRLML2502")
      (footprint "SOT-23")
      (description "Транзистор MOSFET N-Channel 20В 4.2А")
      (libsource (lib "Schlib") (part "IRLML2502"))
    )
    (comp (ref "VD13")
      (value "IRLML2502")
      (footprint "SOT-23")
      (description "Транзистор MOSFET N-Channel 20В 4.2А")
      (libsource (lib "Schlib") (part "IRLML2502"))
    )
    (comp (ref "VD14")
      (value "IRLML2502")
      (footprint "SOT-23")
      (description "Транзистор MOSFET N-Channel 20В 4.2А")
      (libsource (lib "Schlib") (part "IRLML2502"))
    )
    (comp (ref "VD15")
      (value "MBR20100CT 100В 20А")
      (footprint "TO220-3 bent")
      (description "Диод TO220 100В 20А")
      (libsource (lib "Schlib") (part "MBR20100CT"))
    )
    (comp (ref "VD16")
      (value "1N4148WS 100В 150мА")
      (footprint "SOD-323")
      (description "Диод SOD-323 100В 150мА")
      (libsource (lib "Schlib") (part "1N4148WS"))
    )
    (comp (ref "VD17")
      (value "USBLC6-2SC6, SOT23-6L")
      (footprint "SOT23-6L")
      (description "Диод USBLC6-2SC6, SOT23-6L")
      (libsource (lib "Schlib") (part "USBLC6-2SC6, SOT23-6L"))
    )
    (comp (ref "VS1")
      (value "BTA16-600BRG")
      (footprint "TO220-3 bent")
      (description "Симистор BTA16-600BRG, TO-220AB")
      (libsource (lib "Schlib") (part "BTA16-600BRG, TO-220AB"))
    )
    (comp (ref "VS2")
      (value "BTA16-600BRG")
      (footprint "TO220-3 bent")
      (description "Симистор BTA16-600BRG, TO-220AB")
      (libsource (lib "Schlib") (part "BTA16-600BRG, TO-220AB"))
    )
    (comp (ref "VT1")
      (value "STP4NK60ZFP")
      (footprint "TO-220FP")
      (description "Транзистор MOSFET N-Ch 600В 4А")
      (libsource (lib "Schlib") (part "STP4NK60ZFP"))
    )
    (comp (ref "VT2")
      (value "2SK2232-VB")
      (footprint "TO-220FP")
      (description "Транзистор MOSFET N-Ch 60В 45А")
      (libsource (lib "Schlib") (part "2SK2232-VB"))
    )
    (comp (ref "X1")
      (value "PLS-4")
      (footprint "PLS 2.54-4")
      (description "Разъем PLS-4, шаг 2.54 мм")
      (libsource (lib "Schlib") (part "PLS-4"))
    )
    (comp (ref "X2")
      (value "2EDGVC-5.0-03P-14-00A(H)")
      (footprint "2EDGVC-5.0-03P-14-00AH")
      (description "Разъем 2EDGVC-5.0-03P-14-00A(H)")
      (libsource (lib "Schlib") (part "2EDGVC-5.0-03P-14-00A(H)"))
    )
    (comp (ref "X3")
      (value "2EDGVC-5.0-02P-14-00A(H)")
      (footprint "2EDGVC-5.0-02P-14-00AH")
      (description "Разъем 2EDGVC-5.0-02P-14-00A(H)")
      (libsource (lib "Schlib") (part "2EDGVC-5.0-02P-14-00A(H)"))
    )
    (comp (ref "X4")
      (value "2EDGVC-5.0-02P-14-00A(H)")
      (footprint "2EDGVC-5.0-02P-14-00AH")
      (description "Разъем 2EDGVC-5.0-02P-14-00A(H)")
      (libsource (lib "Schlib") (part "2EDGVC-5.0-02P-14-00A(H)"))
    )
    (comp (ref "X5")
      (value "2EDGVC-5.0-02P-14-00A(H)")
      (footprint "2EDGVC-5.0-02P-14-00AH")
      (description "Разъем 2EDGVC-5.0-02P-14-00A(H)")
      (libsource (lib "Schlib") (part "2EDGVC-5.0-02P-14-00A(H)"))
    )
    (comp (ref "X6")
      (value "2EDGVC-5.0-02P-14-00A(H)")
      (footprint "2EDGVC-5.0-02P-14-00AH")
      (description "Разъем 2EDGVC-5.0-02P-14-00A(H)")
      (libsource (lib "Schlib") (part "2EDGVC-5.0-02P-14-00A(H)"))
    )
    (comp (ref "X7")
      (value "2EDGVC-5.0-02P-14-00A(H)")
      (footprint "2EDGVC-5.0-02P-14-00AH")
      (description "Разъем 2EDGVC-5.0-02P-14-00A(H)")
      (libsource (lib "Schlib") (part "2EDGVC-5.0-02P-14-00A(H)"))
    )
    (comp (ref "X8")
      (value "2EDGVC-5.0-02P-14-00A(H)")
      (footprint "2EDGVC-5.0-02P-14-00AH")
      (description "Разъем 2EDGVC-5.0-02P-14-00A(H)")
      (libsource (lib "Schlib") (part "2EDGVC-5.0-02P-14-00A(H)"))
    )
    (comp (ref "X9")
      (value "IDC-40MS")
      (footprint "PLS-2x40")
      (description "Разъем шлейф на плату 40 pin шаг 2.54 мм")
      (libsource (lib "Schlib") (part "BH-40 (DS1013-40S) (IDC-40MS)"))
    )
    (comp (ref "X10")
      (value "WF-3")
      (footprint "WF-3")
      (description "Разъем WF-3")
      (libsource (lib "Schlib") (part "WF-3"))
    )
    (comp (ref "X11")
      (value "2EDGVC-5.0-02P-14-00A(H)")
      (footprint "2EDGVC-5.0-02P-14-00AH")
      (description "Разъем 2EDGVC-5.0-02P-14-00A(H)")
      (libsource (lib "Schlib") (part "2EDGVC-5.0-02P-14-00A(H)"))
    )
  )
  (nets
    (net (code "1") (name "+3V3") (class "Default")
      (node (ref "C26") (pin "2") (pinfunction "2_2") (pintype "passive"))
      (node (ref "C27") (pin "2") (pinfunction "2_2") (pintype "passive"))
      (node (ref "C28") (pin "2") (pinfunction "2_2") (pintype "passive"))
      (node (ref "C29") (pin "2") (pinfunction "2_2") (pintype "passive"))
      (node (ref "DD2") (pin "1") (pinfunction "VBAT_1") (pintype "passive"))
      (node (ref "DD2") (pin "24") (pinfunction "VDD_1_24") (pintype "passive"))
      (node (ref "DD2") (pin "36") (pinfunction "VDD_2_36") (pintype "passive"))
      (node (ref "DD2") (pin "48") (pinfunction "VDD_3_48") (pintype "passive"))
      (node (ref "L2") (pin "1") (pinfunction "1_1") (pintype "passive"))
      (node (ref "R1") (pin "1") (pinfunction "1_1") (pintype "passive"))
      (node (ref "R35") (pin "1") (pinfunction "1_1") (pintype "passive"))
      (node (ref "R38") (pin "2") (pinfunction "2_2") (pintype "passive"))
      (node (ref "R39") (pin "2") (pinfunction "2_2") (pintype "passive"))
      (node (ref "R7") (pin "1") (pinfunction "1_1") (pintype "passive"))
      (node (ref "U2") (pin "5") (pinfunction "VOUT_5") (pintype "passive"))
      (node (ref "VD17") (pin "5") (pinfunction "5_5") (pintype "passive"))
      (node (ref "VD8") (pin "3") (pinfunction "3_3") (pintype "passive"))
      (node (ref "VD9") (pin "3") (pinfunction "3_3") (pintype "passive"))
      (node (ref "X1") (pin "1") (pinfunction "1_1") (pintype "passive"))
      (node (ref "X9") (pin "5") (pinfunction "5_5") (pintype "passive"))
      (node (ref "X9") (pin "6") (pinfunction "6_6") (pintype "passive"))
    )
    (net (code "2") (name "+3V3A") (class "Default")
      (node (ref "C24") (pin "2") (pinfunction "2_2") (pintype "passive"))
      (node (ref "C25") (pin "2") (pinfunction "2_2") (pintype "passive"))
      (node (ref "DD2") (pin "9") (pinfunction "VDDA_9") (pintype "passive"))
      (node (ref "L2") (pin "2") (pinfunction "2_2") (pintype "passive"))
      (node (ref "R42") (pin "2") (pinfunction "2_2") (pintype "passive"))
      (node (ref "R43") (pin "2") (pinfunction "2_2") (pintype "passive"))
      (node (ref "R54") (pin "1") (pinfunction "1_1") (pintype "passive"))
      (node (ref "VD10") (pin "3") (pinfunction "3_3") (pintype "passive"))
      (node (ref "VD11") (pin "3") (pinfunction "3_3") (pintype "passive"))
    )
    (net (code "3") (name "+5V") (class "Default")
      (node (ref "C43") (pin "2") (pinfunction "2_2") (pintype "passive"))
      (node (ref "U1") (pin "2") (pinfunction "OUT_2") (pintype "passive"))
      (node (ref "U2") (pin "1") (pinfunction "VIN_1") (pintype "passive"))
      (node (ref "U2") (pin "3") (pinfunction "EN_3") (pintype "passive"))
      (node (ref "X9") (pin "1") (pinfunction "1_1") (pintype "passive"))
      (node (ref "X9") (pin "2") (pinfunction "2_2") (pintype "passive"))
    )
    (net (code "4") (name "+12V") (class "Default")
      (node (ref "C13") (pin "1") (pinfunction "1_1") (pintype "passive"))
      (node (ref "C14") (pin "2") (pinfunction "2_2") (pintype "passive"))
      (node (ref "C15") (pin "2") (pinfunction "2_2") (pintype "passive"))
      (node (ref "C16") (pin "2") (pinfunction "2_2") (pintype "passive"))
      (node (ref "C41") (pin "2") (pinfunction "2_2") (pintype "passive"))
      (node (ref "C47") (pin "2") (pinfunction "2_2") (pintype "passive"))
      (node (ref "C48") (pin "2") (pinfunction "2_2") (pintype "passive"))
      (node (ref "R28") (pin "2") (pinfunction "2_2") (pintype "passive"))
      (node (ref "R30") (pin "2") (pinfunction "2_2") (pintype "passive"))
      (node (ref "U1") (pin "3") (pinfunction "IN_3") (pintype "passive"))
      (node (ref "U3") (pin "1") (pinfunction "VDD_1") (pintype "passive"))
      (node (ref "VD15") (pin "2") (pinfunction "2_2") (pintype "passive"))
      (node (ref "VD7") (pin "2") (pinfunction "2_2") (pintype "passive"))
      (node (ref "X10") (pin "1") (pinfunction "1_1") (pintype "passive"))
      (node (ref "X11") (pin "1") (pinfunction "1_1") (pintype "passive"))
      (node (ref "X9") (pin "39") (pinfunction "39_39") (pintype "passive"))
      (node (ref "X9") (pin "40") (pinfunction "40_40") (pintype "passive"))
    )
    (net (code "5") (name "+PVCC") (class "Default")
      (node (ref "C3") (pin "2") (pinfunction "2_2") (pintype "passive"))
      (node (ref "C4") (pin "2") (pinfunction "2_2") (pintype "passive"))
      (node (ref "DD1") (pin "1") (pinfunction "VCC_1") (pintype "passive"))
      (node (ref "R25") (pin "1") (pinfunction "1_1") (pintype "passive"))
      (node (ref "R61") (pin "2") (pinfunction "2_2") (pintype "passive"))
      (node (ref "R62") (pin "2") (pinfunction "2_2") (pintype "passive"))
      (node (ref "VD6") (pin "2") (pinfunction "1.27_2") (pintype "passive"))
    )
    (net (code "6") (name "/400V") (class "Default")
      (node (ref "C5") (pin "1") (pinfunction "1_1") (pintype "passive"))
      (node (ref "C6") (pin "2") (pinfunction "2_2") (pintype "passive"))
      (node (ref "C7") (pin "2") (pinfunction "2_2") (pintype "passive"))
      (node (ref "R17") (pin "2") (pinfunction "2_2") (pintype "passive"))
      (node (ref "R19") (pin "2") (pinfunction "2_2") (pintype "passive"))
      (node (ref "T1") (pin "1") (pinfunction "1_1") (pintype "passive"))
      (node (ref "VD1") (pin "1") (pinfunction "1_1") (pintype "passive"))
    )
    (net (code "7") (name "/400V_PWM") (class "Default")
      (node (ref "T1") (pin "2") (pinfunction "2_2") (pintype "passive"))
      (node (ref "VD3") (pin "1") (pinfunction "1_1") (pintype "passive"))
      (node (ref "VT1") (pin "3") (pinfunction "D_3") (pintype "passive"))
    )
    (net (code "8") (name "/AC{slash}L{slash}F") (class "Default")
      (node (ref "C20") (pin "2") (pinfunction "2_2") (pintype "passive"))
      (node (ref "C22") (pin "2") (pinfunction "2_2") (pintype "passive"))
      (node (ref "L1") (pin "3") (pinfunction "3_3") (pintype "passive"))
      (node (ref "R59") (pin "2") (pinfunction "2_2") (pintype "passive"))
      (node (ref "VD1") (pin "4") (pinfunction "4_4") (pintype "passive"))
    )
    (net (code "9") (name "/AC{slash}N{slash}F") (class "Default")
      (node (ref "C22") (pin "1") (pinfunction "1_1") (pintype "passive"))
      (node (ref "C23") (pin "1") (pinfunction "1_1") (pintype "passive"))
      (node (ref "L1") (pin "2") (pinfunction "2_2") (pintype "passive"))
      (node (ref "R60") (pin "2") (pinfunction "2_2") (pintype "passive"))
      (node (ref "VD1") (pin "3") (pinfunction "3_3") (pintype "passive"))
    )
    (net (code "10") (name "/Boot0") (class "Default")
      (node (ref "DD2") (pin "44") (pinfunction "PD3/BOOT0_44") (pintype "passive"))
      (node (ref "R33") (pin "2") (pinfunction "2_2") (pintype "passive"))
    )
    (net (code "11") (name "/DRV") (class "Default")
      (node (ref "DD1") (pin "3") (pinfunction "DRV_3") (pintype "passive"))
      (node (ref "R14") (pin "1") (pinfunction "1_1") (pintype "passive"))
    )
    (net (code "12") (name "/Isense") (class "Default")
      (node (ref "DD1") (pin "4") (pinfunction "ISENSE_4") (pintype "passive"))
      (node (ref "R13") (pin "1") (pinfunction "1_1") (pintype "passive"))
    )
    (net (code "13") (name "/Reset") (class "Default")
      (node (ref "C40") (pin "1") (pinfunction "1_1") (pintype "passive"))
      (node (ref "DD2") (pin "7") (pinfunction "NRST_7") (pintype "passive"))
      (node (ref "R35") (pin "2") (pinfunction "2_2") (pintype "passive"))
    )
    (net (code "14") (name "/Vsense") (class "Default")
      (node (ref "C17") (pin "1") (pinfunction "1_1") (pintype "passive"))
      (node (ref "D1") (pin "2") (pinfunction "Emitter_2") (pintype "passive"))
      (node (ref "R30") (pin "1") (pinfunction "1_1") (pintype "passive"))
      (node (ref "R31") (pin "2") (pinfunction "2_2") (pintype "passive"))
      (node (ref "R32") (pin "2") (pinfunction "2_2") (pintype "passive"))
    )
    (net (code "15") (name "AC_MOTOR") (class "Default")
      (node (ref "DD2") (pin "19") (pinfunction "PB1_19") (pintype "passive"))
      (node (ref "R9") (pin "1") (pinfunction "1_1") (pintype "passive"))
    )
    (net (code "16") (name "AC{slash}L") (class "Default")
      (node (ref "C1") (pin "2") (pinfunction "2_2") (pintype "passive"))
      (node (ref "C2") (pin "2") (pinfunction "2_2") (pintype "passive"))
      (node (ref "C21") (pin "2") (pinfunction "2_2") (pintype "passive"))
      (node (ref "L1") (pin "4") (pinfunction "4_4") (pintype "passive"))
      (node (ref "R2") (pin "2") (pinfunction "2_2") (pintype "passive"))
      (node (ref "R8") (pin "2") (pinfunction "2_2") (pintype "passive"))
      (node (ref "RU1") (pin "1") (pinfunction "1_1") (pintype "passive"))
      (node (ref "VS1") (pin "2") (pinfunction "A2_2") (pintype "passive"))
      (node (ref "VS2") (pin "2") (pinfunction "A2_2") (pintype "passive"))
      (node (ref "X2") (pin "3") (pinfunction "3_3") (pintype "passive"))
    )
    (net (code "17") (name "AC{slash}N") (class "Default")
      (node (ref "C21") (pin "1") (pinfunction "1_1") (pintype "passive"))
      (node (ref "L1") (pin "1") (pinfunction "1_1") (pintype "passive"))
      (node (ref "RU1") (pin "2") (pinfunction "2_2") (pintype "passive"))
      (node (ref "X2") (pin "1") (pinfunction "1_1") (pintype "passive"))
      (node (ref "X3") (pin "1") (pinfunction "1_1") (pintype "passive"))
      (node (ref "X4") (pin "1") (pinfunction "1_1") (pintype "passive"))
    )
    (net (code "18") (name "AGND") (class "Default")
      (node (ref "C24") (pin "1") (pinfunction "1_1") (pintype "passive"))
      (node (ref "C25") (pin "1") (pinfunction "1_1") (pintype "passive"))
      (node (ref "C33") (pin "1") (pinfunction "1_1") (pintype "passive"))
      (node (ref "C34") (pin "1") (pinfunction "1_1") (pintype "passive"))
      (node (ref "C46") (pin "1") (pinfunction "1_1") (pintype "passive"))
      (node (ref "DD2") (pin "8") (pinfunction "VSSA_8") (pintype "passive"))
      (node (ref "R34") (pin "2") (pinfunction "2_2") (pintype "passive"))
      (node (ref "VD10") (pin "1") (pinfunction "1_1") (pintype "passive"))
      (node (ref "VD11") (pin "1") (pinfunction "1_1") (pintype "passive"))
    )
    (net (code "19") (name "Cooler") (class "Default")
      (node (ref "DD2") (pin "29") (pinfunction "PA8_29") (pintype "passive"))
      (node (ref "R55") (pin "1") (pinfunction "1_1") (pintype "passive"))
    )
    (net (code "20") (name "DC_MOTOR") (class "Default")
      (node (ref "DD2") (pin "30") (pinfunction "PA9_30") (pintype "passive"))
      (node (ref "R57") (pin "1") (pinfunction "1_1") (pintype "passive"))
    )
    (net (code "21") (name "Display_BS1") (class "Default")
      (node (ref "DD2") (pin "26") (pinfunction "PB13_26") (pintype "passive"))
      (node (ref "X9") (pin "32") (pinfunction "32_32") (pintype "passive"))
    )
    (net (code "22") (name "Display_BS2") (class "Default")
      (node (ref "DD2") (pin "25") (pinfunction "PB12_25") (pintype "passive"))
      (node (ref "X9") (pin "33") (pinfunction "33_33") (pintype "passive"))
    )
    (net (code "23") (name "Display_BackLight") (class "Default")
      (node (ref "DD2") (pin "31") (pinfunction "PA10_31") (pintype "passive"))
      (node (ref "X9") (pin "28") (pinfunction "28_28") (pintype "passive"))
    )
    (net (code "24") (name "Display_DB0") (class "Default")
      (node (ref "DD2") (pin "42") (pinfunction "PB6_42") (pintype "passive"))
      (node (ref "X9") (pin "22") (pinfunction "22_22") (pintype "passive"))
    )
    (net (code "25") (name "Display_DB1") (class "Default")
      (node (ref "DD2") (pin "43") (pinfunction "PB7_43") (pintype "passive"))
      (node (ref "X9") (pin "21") (pinfunction "21_21") (pintype "passive"))
    )
    (net (code "26") (name "Display_DB2") (class "Default")
      (node (ref "DD2") (pin "21") (pinfunction "PB10_21") (pintype "passive"))
      (node (ref "X9") (pin "20") (pinfunction "20_20") (pintype "passive"))
    )
    (net (code "27") (name "Display_DB3") (class "Default")
      (node (ref "DD2") (pin "39") (pinfunction "PB3_39") (pintype "passive"))
      (node (ref "X9") (pin "19") (pinfunction "19_19") (pintype "passive"))
    )
    (net (code "28") (name "Display_DB4") (class "Default")
      (node (ref "DD2") (pin "40") (pinfunction "PB4_40") (pintype "passive"))
      (node (ref "X9") (pin "18") (pinfunction "18_18") (pintype "passive"))
    )
    (net (code "29") (name "Display_DB5") (class "Default")
      (node (ref "DD2") (pin "41") (pinfunction "PB5_41") (pintype "passive"))
      (node (ref "X9") (pin "17") (pinfunction "17_17") (pintype "passive"))
    )
    (net (code "30") (name "Display_DB6") (class "Default")
      (node (ref "DD2") (pin "46") (pinfunction "PB9_46") (pintype "passive"))
      (node (ref "X9") (pin "16") (pinfunction "16_16") (pintype "passive"))
    )
    (net (code "31") (name "Display_DB7") (class "Default")
      (node (ref "DD2") (pin "45") (pinfunction "PB8_45") (pintype "passive"))
      (node (ref "X9") (pin "15") (pinfunction "15_15") (pintype "passive"))
    )
    (net (code "32") (name "Display_E") (class "Default")
      (node (ref "DD2") (pin "32") (pinfunction "PA11_32") (pintype "passive"))
      (node (ref "X9") (pin "23") (pinfunction "23_23") (pintype "passive"))
    )
    (net (code "33") (name "Display_RS") (class "Default")
      (node (ref "DD2") (pin "27") (pinfunction "PB14_27") (pintype "passive"))
      (node (ref "X9") (pin "25") (pinfunction "25_25") (pintype "passive"))
    )
    (net (code "34") (name "Display_RW") (class "Default")
      (node (ref "DD2") (pin "33") (pinfunction "PA12_33") (pintype "passive"))
      (node (ref "X9") (pin "24") (pinfunction "24_24") (pintype "passive"))
    )
    (net (code "35") (name "Display_VO") (class "Default")
      (node (ref "DD2") (pin "28") (pinfunction "PB15_28") (pintype "passive"))
      (node (ref "X9") (pin "26") (pinfunction "26_26") (pintype "passive"))
    )
    (net (code "36") (name "EGND") (class "Default")
      (node (ref "C19") (pin "2") (pinfunction "2_2") (pintype "passive"))
      (node (ref "C20") (pin "1") (pinfunction "1_1") (pintype "passive"))
      (node (ref "C23") (pin "2") (pinfunction "2_2") (pintype "passive"))
      (node (ref "X2") (pin "2") (pinfunction "2_2") (pintype "passive"))
    )
    (net (code "37") (name "GND") (class "Default")
      (node (ref "C14") (pin "1") (pinfunction "1_1") (pintype "passive"))
      (node (ref "C15") (pin "1") (pinfunction "1_1") (pintype "passive"))
      (node (ref "C16") (pin "1") (pinfunction "1_1") (pintype "passive"))
      (node (ref "C19") (pin "1") (pinfunction "1_1") (pintype "passive"))
      (node (ref "C26") (pin "1") (pinfunction "1_1") (pintype "passive"))
      (node (ref "C27") (pin "1") (pinfunction "1_1") (pintype "passive"))
      (node (ref "C28") (pin "1") (pinfunction "1_1") (pintype "passive"))
      (node (ref "C29") (pin "1") (pinfunction "1_1") (pintype "passive"))
      (node (ref "C31") (pin "1") (pinfunction "1_1") (pintype "passive"))
      (node (ref "C32") (pin "1") (pinfunction "1_1") (pintype "passive"))
      (node (ref "C35") (pin "2") (pinfunction "2_2") (pintype "passive"))
      (node (ref "C36") (pin "2") (pinfunction "2_2") (pintype "passive"))
      (node (ref "C37") (pin "2") (pinfunction "2_2") (pintype "passive"))
      (node (ref "C38") (pin "2") (pinfunction "2_2") (pintype "passive"))
      (node (ref "C39") (pin "2") (pinfunction "2_2") (pintype "passive"))
      (node (ref "C40") (pin "2") (pinfunction "2_2") (pintype "passive"))
      (node (ref "C41") (pin "1") (pinfunction "1_1") (pintype "passive"))
      (node (ref "C43") (pin "1") (pinfunction "1_1") (pintype "passive"))
      (node (ref "C45") (pin "1") (pinfunction "1_1") (pintype "passive"))
      (node (ref "C48") (pin "1") (pinfunction "1_1") (pintype "passive"))
      (node (ref "C49") (pin "2") (pinfunction "2_2") (pintype "passive"))
      (node (ref "C50") (pin "2") (pinfunction "2_2") (pintype "passive"))
      (node (ref "C51") (pin "2") (pinfunction "2_2") (pintype "passive"))
      (node (ref "C52") (pin "2") (pinfunction "2_2") (pintype "passive"))
      (node (ref "D1") (pin "3") (pinfunction "Collector_3") (pintype "passive"))
      (node (ref "DD2") (pin "23") (pinfunction "VSS_1_23") (pintype "passive"))
      (node (ref "DD2") (pin "35") (pinfunction "VSS_2_35") (pintype "passive"))
      (node (ref "DD2") (pin "47") (pinfunction "VSS_3_47") (pintype "passive"))
      (node (ref "Q1") (pin "3") (pinfunction "3_3") (pintype "passive"))
      (node (ref "R32") (pin "1") (pinfunction "1_1") (pintype "passive"))
      (node (ref "R33") (pin "1") (pinfunction "1_1") (pintype "passive"))
      (node (ref "R34") (pin "1") (pinfunction "1_1") (pintype "passive"))
      (node (ref "R44") (pin "1") (pinfunction "1_1") (pintype "passive"))
      (node (ref "R46") (pin "1") (pinfunction "1_1") (pintype "passive"))
      (node (ref "R48") (pin "1") (pinfunction "1_1") (pintype "passive"))
      (node (ref "R50") (pin "1") (pinfunction "1_1") (pintype "passive"))
      (node (ref "R52") (pin "1") (pinfunction "1_1") (pintype "passive"))
      (node (ref "RT1") (pin "2") (pinfunction "2_2") (pintype "passive"))
      (node (ref "T1") (pin "8") (pinfunction "8_8") (pintype "passive"))
      (node (ref "U1") (pin "1") (pinfunction "GND_1") (pintype "passive"))
      (node (ref "U2") (pin "2") (pinfunction "GND_2") (pintype "passive"))
      (node (ref "U3") (pin "2") (pinfunction "GND_2") (pintype "passive"))
      (node (ref "VD12") (pin "2") (pinfunction "S_2") (pintype "passive"))
      (node (ref "VD13") (pin "2") (pinfunction "S_2") (pintype "passive"))
      (node (ref "VD14") (pin "2") (pinfunction "S_2") (pintype "passive"))
      (node (ref "VD17") (pin "2") (pinfunction "2_2") (pintype "passive"))
      (node (ref "VD8") (pin "1") (pinfunction "1_1") (pintype "passive"))
      (node (ref "VD9") (pin "1") (pinfunction "1_1") (pintype "passive"))
      (node (ref "VT2") (pin "2") (pinfunction "S_2") (pintype "passive"))
      (node (ref "X1") (pin "4") (pinfunction "4_4") (pintype "passive"))
      (node (ref "X5") (pin "2") (pinfunction "2_2") (pintype "passive"))
      (node (ref "X6") (pin "2") (pinfunction "2_2") (pintype "passive"))
      (node (ref "X7") (pin "2") (pinfunction "2_2") (pintype "passive"))
      (node (ref "X8") (pin "2") (pinfunction "2_2") (pintype "passive"))
      (node (ref "X9") (pin "14") (pinfunction "14_14") (pintype "passive"))
      (node (ref "X9") (pin "29") (pinfunction "29_29") (pintype "passive"))
      (node (ref "X9") (pin "3") (pinfunction "3_3") (pintype "passive"))
      (node (ref "X9") (pin "31") (pinfunction "31_31") (pintype "passive"))
      (node (ref "X9") (pin "34") (pinfunction "34_34") (pintype "passive"))
      (node (ref "X9") (pin "36") (pinfunction "36_36") (pintype "passive"))
      (node (ref "X9") (pin "37") (pinfunction "37_37") (pintype "passive"))
      (node (ref "X9") (pin "38") (pinfunction "38_38") (pintype "passive"))
      (node (ref "X9") (pin "4") (pinfunction "4_4") (pintype "passive"))
      (node (ref "X9") (pin "7") (pinfunction "7_7") (pintype "passive"))
      (node (ref "X9") (pin "8") (pinfunction "8_8") (pintype "passive"))
    )
    (net (code "38") (name "HEATER") (class "Default")
      (node (ref "DD2") (pin "20") (pinfunction "PB2_20") (pintype "passive"))
      (node (ref "R3") (pin "1") (pinfunction "1_1") (pintype "passive"))
    )
    (net (code "39") (name "LEFT_BUTTON") (class "Default")
      (node (ref "C38") (pin "1") (pinfunction "1_1") (pintype "passive"))
      (node (ref "DD2") (pin "17") (pinfunction "PA7_17") (pintype "passive"))
      (node (ref "R50") (pin "2") (pinfunction "2_2") (pintype "passive"))
      (node (ref "R51") (pin "1") (pinfunction "1_1") (pintype "passive"))
    )
    (net (code "40") (name "LEFT_BUTTON_C") (class "Default")
      (node (ref "R51") (pin "2") (pinfunction "2_2") (pintype "passive"))
      (node (ref "X9") (pin "12") (pinfunction "12_12") (pintype "passive"))
    )
    (net (code "41") (name "Led_R") (class "Default")
      (node (ref "DD2") (pin "22") (pinfunction "PB11_22") (pintype "passive"))
      (node (ref "X9") (pin "35") (pinfunction "35_35") (pintype "passive"))
    )
    (net (code "42") (name "MENU_BUTTON") (class "Default")
      (node (ref "C37") (pin "1") (pinfunction "1_1") (pintype "passive"))
      (node (ref "DD2") (pin "16") (pinfunction "PA6_16") (pintype "passive"))
      (node (ref "R48") (pin "2") (pinfunction "2_2") (pintype "passive"))
      (node (ref "R49") (pin "1") (pinfunction "1_1") (pintype "passive"))
    )
    (net (code "43") (name "MENU_BUTTON_C") (class "Default")
      (node (ref "R49") (pin "2") (pinfunction "2_2") (pintype "passive"))
      (node (ref "X9") (pin "11") (pinfunction "11_11") (pintype "passive"))
    )
    (net (code "44") (name "Net-(C1-Pad1)") (class "Default")
      (node (ref "C1") (pin "1") (pinfunction "1_1") (pintype "passive"))
      (node (ref "R4") (pin "2") (pinfunction "2_2") (pintype "passive"))
    )
    (net (code "45") (name "Net-(C2-Pad1)") (class "Default")
      (node (ref "C2") (pin "1") (pinfunction "1_1") (pintype "passive"))
      (node (ref "R10") (pin "2") (pinfunction "2_2") (pintype "passive"))
    )
    (net (code "46") (name "Net-(C9-Pad2)") (class "Default")
      (node (ref "C9") (pin "2") (pinfunction "2_2") (pintype "passive"))
      (node (ref "R13") (pin "2") (pinfunction "2_2") (pintype "passive"))
      (node (ref "R16") (pin "1") (pinfunction "1_1") (pintype "passive"))
    )
    (net (code "47") (name "Net-(C13-Pad2)") (class "Default")
      (node (ref "C13") (pin "2") (pinfunction "2_2") (pintype "passive"))
      (node (ref "R27") (pin "2") (pinfunction "2_2") (pintype "passive"))
    )
    (net (code "48") (name "Net-(C18-Pad1)") (class "Default")
      (node (ref "C18") (pin "1") (pinfunction "1_1") (pintype "passive"))
      (node (ref "R31") (pin "1") (pinfunction "1_1") (pintype "passive"))
    )
    (net (code "49") (name "Net-(D1-Base)") (class "Default")
      (node (ref "C17") (pin "2") (pinfunction "2_2") (pintype "passive"))
      (node (ref "C18") (pin "2") (pinfunction "2_2") (pintype "passive"))
      (node (ref "D1") (pin "1") (pinfunction "Base_1") (pintype "passive"))
      (node (ref "DA3") (pin "2") (pinfunction "2_2") (pintype "passive"))
    )
    (net (code "50") (name "Net-(DA1-LED_A)") (class "Default")
      (node (ref "DA1") (pin "1") (pinfunction "LED_A_1") (pintype "passive"))
      (node (ref "R1") (pin "2") (pinfunction "2_2") (pintype "passive"))
    )
    (net (code "51") (name "Net-(DA1-LED_C)") (class "Default")
      (node (ref "DA1") (pin "2") (pinfunction "LED_C_2") (pintype "passive"))
      (node (ref "VD12") (pin "3") (pinfunction "D_3") (pintype "passive"))
    )
    (net (code "52") (name "Net-(DA1-Uout-Pad6)") (class "Default")
      (node (ref "DA1") (pin "6") (pinfunction "Uout_6") (pintype "passive"))
      (node (ref "R2") (pin "1") (pinfunction "1_1") (pintype "passive"))
    )
    (net (code "53") (name "Net-(DA2-LED_A)") (class "Default")
      (node (ref "DA2") (pin "1") (pinfunction "LED_A_1") (pintype "passive"))
      (node (ref "R7") (pin "2") (pinfunction "2_2") (pintype "passive"))
    )
    (net (code "54") (name "Net-(DA2-LED_C)") (class "Default")
      (node (ref "DA2") (pin "2") (pinfunction "LED_C_2") (pintype "passive"))
      (node (ref "VD13") (pin "3") (pinfunction "D_3") (pintype "passive"))
    )
    (net (code "55") (name "Net-(DA2-Uout-Pad6)") (class "Default")
      (node (ref "DA2") (pin "6") (pinfunction "Uout_6") (pintype "passive"))
      (node (ref "R8") (pin "1") (pinfunction "1_1") (pintype "passive"))
    )
    (net (code "56") (name "Net-(DA3-Pad1)") (class "Default")
      (node (ref "DA3") (pin "1") (pinfunction "1_1") (pintype "passive"))
      (node (ref "R28") (pin "1") (pinfunction "1_1") (pintype "passive"))
    )
    (net (code "57") (name "Net-(DD1-CTRL)") (class "Default")
      (node (ref "C11") (pin "2") (pinfunction "2_2") (pintype "passive"))
      (node (ref "DA3") (pin "4") (pinfunction "4_4") (pintype "passive"))
      (node (ref "DD1") (pin "7") (pinfunction "CTRL_7") (pintype "passive"))
    )
    (net (code "58") (name "Net-(DD1-OPTIMER)") (class "Default")
      (node (ref "C12") (pin "2") (pinfunction "2_2") (pintype "passive"))
      (node (ref "DD1") (pin "8") (pinfunction "OPTIMER_8") (pintype "passive"))
      (node (ref "R26") (pin "2") (pinfunction "2_2") (pintype "passive"))
    )
    (net (code "59") (name "Net-(DD1-PROTECT)") (class "Default")
      (node (ref "C10") (pin "1") (pinfunction "1_1") (pintype "passive"))
      (node (ref "DD1") (pin "6") (pinfunction "PROTECT_6") (pintype "passive"))
      (node (ref "RT2") (pin "1") (pinfunction "1_1") (pintype "passive"))
      (node (ref "VD6") (pin "1") (pinfunction "1_1") (pintype "passive"))
    )
    (net (code "60") (name "Net-(DD1-VSENSE)") (class "Default")
      (node (ref "C8") (pin "2") (pinfunction "2_2") (pintype "passive"))
      (node (ref "DD1") (pin "5") (pinfunction "VSENSE_5") (pintype "passive"))
      (node (ref "R21") (pin "1") (pinfunction "1_1") (pintype "passive"))
      (node (ref "R23") (pin "1") (pinfunction "1_1") (pintype "passive"))
    )
    (net (code "61") (name "Net-(DD2-PC14{slash}OSC32_IN)") (class "Default")
      (node (ref "C49") (pin "1") (pinfunction "1_1") (pintype "passive"))
      (node (ref "DD2") (pin "3") (pinfunction "PC14/OSC32_IN_3") (pintype "passive"))
      (node (ref "Q1") (pin "2") (pinfunction "2_2") (pintype "passive"))
    )
    (net (code "62") (name "Net-(DD2-PC15{slash}OSC32_OUT)") (class "Default")
      (node (ref "C50") (pin "1") (pinfunction "1_1") (pintype "passive"))
      (node (ref "DD2") (pin "4") (pinfunction "PC15/OSC32_OUT_4") (pintype "passive"))
      (node (ref "Q1") (pin "1") (pinfunction "1_1") (pintype "passive"))
    )
    (net (code "63") (name "Net-(DD2-PD0{slash}OSC_IN)") (class "Default")
      (node (ref "C51") (pin "1") (pinfunction "1_1") (pintype "passive"))
      (node (ref "DD2") (pin "5") (pinfunction "PD0/OSC_IN_5") (pintype "passive"))
      (node (ref "Q2") (pin "1") (pinfunction "1_1") (pintype "passive"))
    )
    (net (code "64") (name "Net-(DD2-PD1{slash}OSC_OUR)") (class "Default")
      (node (ref "C52") (pin "1") (pinfunction "1_1") (pintype "passive"))
      (node (ref "DD2") (pin "6") (pinfunction "PD1/OSC_OUR_6") (pintype "passive"))
      (node (ref "Q2") (pin "2") (pinfunction "2_2") (pintype "passive"))
    )
    (net (code "65") (name "Net-(R4-Pad1)") (class "Default")
      (node (ref "R4") (pin "1") (pinfunction "1_1") (pintype "passive"))
      (node (ref "R6") (pin "1") (pinfunction "1_1") (pintype "passive"))
    )
    (net (code "66") (name "Net-(R10-Pad1)") (class "Default")
      (node (ref "R10") (pin "1") (pinfunction "1_1") (pintype "passive"))
      (node (ref "R12") (pin "1") (pinfunction "1_1") (pintype "passive"))
    )
    (net (code "67") (name "Net-(R17-Pad1)") (class "Default")
      (node (ref "R17") (pin "1") (pinfunction "1_1") (pintype "passive"))
      (node (ref "R18") (pin "1") (pinfunction "1_1") (pintype "passive"))
    )
    (net (code "68") (name "Net-(R19-Pad1)") (class "Default")
      (node (ref "R19") (pin "1") (pinfunction "1_1") (pintype "passive"))
      (node (ref "R20") (pin "1") (pinfunction "1_1") (pintype "passive"))
    )
    (net (code "69") (name "Net-(R20-Pad2)") (class "Default")
      (node (ref "R20") (pin "2") (pinfunction "2_2") (pintype "passive"))
      (node (ref "R22") (pin "2") (pinfunction "2_2") (pintype "passive"))
    )
    (net (code "70") (name "Net-(R27-Pad1)") (class "Default")
      (node (ref "R27") (pin "1") (pinfunction "1_1") (pintype "passive"))
      (node (ref "T1") (pin "6") (pinfunction "6_6") (pintype "passive"))
      (node (ref "VD7") (pin "1") (pinfunction "1_1") (pintype "passive"))
      (node (ref "VD7") (pin "3") (pinfunction "3_3") (pintype "passive"))
    )
    (net (code "71") (name "Net-(R29-Pad2)") (class "Default")
      (node (ref "R29") (pin "2") (pinfunction "2_2") (pintype "passive"))
      (node (ref "RT2") (pin "2") (pinfunction "2_2") (pintype "passive"))
    )
    (net (code "72") (name "Net-(R36-Pad1)") (class "Default")
      (node (ref "R36") (pin "1") (pinfunction "1_1") (pintype "passive"))
      (node (ref "VD17") (pin "6") (pinfunction "6_6") (pintype "passive"))
    )
    (net (code "73") (name "Net-(R37-Pad1)") (class "Default")
      (node (ref "R37") (pin "1") (pinfunction "1_1") (pintype "passive"))
      (node (ref "VD17") (pin "4") (pinfunction "4_4") (pintype "passive"))
    )
    (net (code "74") (name "Net-(R40-Pad2)") (class "Default")
      (node (ref "R40") (pin "2") (pinfunction "2_2") (pintype "passive"))
      (node (ref "X5") (pin "1") (pinfunction "1_1") (pintype "passive"))
    )
    (net (code "75") (name "Net-(R41-Pad2)") (class "Default")
      (node (ref "R41") (pin "2") (pinfunction "2_2") (pintype "passive"))
      (node (ref "X6") (pin "1") (pinfunction "1_1") (pintype "passive"))
    )
    (net (code "76") (name "Net-(R59-Pad1)") (class "Default")
      (node (ref "R59") (pin "1") (pinfunction "1_1") (pintype "passive"))
      (node (ref "R62") (pin "1") (pinfunction "1_1") (pintype "passive"))
    )
    (net (code "77") (name "Net-(R60-Pad1)") (class "Default")
      (node (ref "R60") (pin "1") (pinfunction "1_1") (pintype "passive"))
      (node (ref "R61") (pin "1") (pinfunction "1_1") (pintype "passive"))
    )
    (net (code "78") (name "Net-(T1-Pad4)") (class "Default")
      (node (ref "T1") (pin "4") (pinfunction "4_4") (pintype "passive"))
      (node (ref "VD5") (pin "1") (pinfunction "1_1") (pintype "passive"))
    )
    (net (code "79") (name "Net-(U2-BYP)") (class "Default")
      (node (ref "C45") (pin "2") (pinfunction "2_2") (pintype "passive"))
      (node (ref "U2") (pin "4") (pinfunction "BYP_4") (pintype "passive"))
    )
    (net (code "80") (name "Net-(U3-IN)") (class "Default")
      (node (ref "R57") (pin "2") (pinfunction "2_2") (pintype "passive"))
      (node (ref "U3") (pin "3") (pinfunction "IN_3") (pintype "passive"))
    )
    (net (code "81") (name "Net-(U3-OUT)") (class "Default")
      (node (ref "R56") (pin "1") (pinfunction "1_1") (pintype "passive"))
      (node (ref "U3") (pin "5") (pinfunction "OUT_5") (pintype "passive"))
    )
    (net (code "82") (name "Net-(VD2-1.27)") (class "Default")
      (node (ref "R14") (pin "2") (pinfunction "2_2") (pintype "passive"))
      (node (ref "R15") (pin "1") (pinfunction "1_1") (pintype "passive"))
      (node (ref "VD2") (pin "2") (pinfunction "1.27_2") (pintype "passive"))
    )
    (net (code "83") (name "Net-(VD3-1.27)") (class "Default")
      (node (ref "C6") (pin "1") (pinfunction "1_1") (pintype "passive"))
      (node (ref "R18") (pin "2") (pinfunction "2_2") (pintype "passive"))
      (node (ref "VD3") (pin "2") (pinfunction "1.27_2") (pintype "passive"))
    )
    (net (code "84") (name "Net-(VD4-1.27)") (class "Default")
      (node (ref "R21") (pin "2") (pinfunction "2_2") (pintype "passive"))
      (node (ref "R22") (pin "1") (pinfunction "1_1") (pintype "passive"))
      (node (ref "VD4") (pin "2") (pinfunction "1.27_2") (pintype "passive"))
    )
    (net (code "85") (name "Net-(VD5-1.27)") (class "Default")
      (node (ref "R25") (pin "2") (pinfunction "2_2") (pintype "passive"))
      (node (ref "VD5") (pin "2") (pinfunction "1.27_2") (pintype "passive"))
    )
    (net (code "86") (name "Net-(VD12-G)") (class "Default")
      (node (ref "R3") (pin "2") (pinfunction "2_2") (pintype "passive"))
      (node (ref "VD12") (pin "1") (pinfunction "G_1") (pintype "passive"))
    )
    (net (code "87") (name "Net-(VD13-G)") (class "Default")
      (node (ref "R9") (pin "2") (pinfunction "2_2") (pintype "passive"))
      (node (ref "VD13") (pin "1") (pinfunction "G_1") (pintype "passive"))
    )
    (net (code "88") (name "Net-(VD14-D)") (class "Default")
      (node (ref "VD14") (pin "3") (pinfunction "D_3") (pintype "passive"))
      (node (ref "X10") (pin "2") (pinfunction "2_2") (pintype "passive"))
    )
    (net (code "89") (name "Net-(VD14-G)") (class "Default")
      (node (ref "R55") (pin "2") (pinfunction "2_2") (pintype "passive"))
      (node (ref "VD14") (pin "1") (pinfunction "G_1") (pintype "passive"))
    )
    (net (code "90") (name "Net-(VD16-1.27)") (class "Default")
      (node (ref "R56") (pin "2") (pinfunction "2_2") (pintype "passive"))
      (node (ref "R58") (pin "1") (pinfunction "1_1") (pintype "passive"))
      (node (ref "VD16") (pin "2") (pinfunction "1.27_2") (pintype "passive"))
    )
    (net (code "91") (name "Net-(VD17-Pad1)") (class "Default")
      (node (ref "VD17") (pin "1") (pinfunction "1_1") (pintype "passive"))
      (node (ref "X1") (pin "3") (pinfunction "3_3") (pintype "passive"))
    )
    (net (code "92") (name "Net-(VD17-Pad3)") (class "Default")
      (node (ref "VD17") (pin "3") (pinfunction "3_3") (pintype "passive"))
      (node (ref "X1") (pin "2") (pinfunction "2_2") (pintype "passive"))
    )
    (net (code "93") (name "Net-(VS1-A1)") (class "Default")
      (node (ref "R5") (pin "1") (pinfunction "1_1") (pintype "passive"))
      (node (ref "R6") (pin "2") (pinfunction "2_2") (pintype "passive"))
      (node (ref "VS1") (pin "1") (pinfunction "A1_1") (pintype "passive"))
      (node (ref "X3") (pin "2") (pinfunction "2_2") (pintype "passive"))
    )
    (net (code "94") (name "Net-(VS1-G)") (class "Default")
      (node (ref "DA1") (pin "4") (pinfunction "Uout_4") (pintype "passive"))
      (node (ref "R5") (pin "2") (pinfunction "2_2") (pintype "passive"))
      (node (ref "VS1") (pin "3") (pinfunction "G_3") (pintype "passive"))
    )
    (net (code "95") (name "Net-(VS2-A1)") (class "Default")
      (node (ref "R11") (pin "1") (pinfunction "1_1") (pintype "passive"))
      (node (ref "R12") (pin "2") (pinfunction "2_2") (pintype "passive"))
      (node (ref "VS2") (pin "1") (pinfunction "A1_1") (pintype "passive"))
      (node (ref "X4") (pin "2") (pinfunction "2_2") (pintype "passive"))
    )
    (net (code "96") (name "Net-(VS2-G)") (class "Default")
      (node (ref "DA2") (pin "4") (pinfunction "Uout_4") (pintype "passive"))
      (node (ref "R11") (pin "2") (pinfunction "2_2") (pintype "passive"))
      (node (ref "VS2") (pin "3") (pinfunction "G_3") (pintype "passive"))
    )
    (net (code "97") (name "Net-(VT1-G)") (class "Default")
      (node (ref "R15") (pin "2") (pinfunction "2_2") (pintype "passive"))
      (node (ref "VD2") (pin "1") (pinfunction "1_1") (pintype "passive"))
      (node (ref "VT1") (pin "1") (pinfunction "G_1") (pintype "passive"))
    )
    (net (code "98") (name "Net-(VT1-S)") (class "Default")
      (node (ref "C9") (pin "1") (pinfunction "1_1") (pintype "passive"))
      (node (ref "R16") (pin "2") (pinfunction "2_2") (pintype "passive"))
      (node (ref "R24") (pin "1") (pinfunction "1_1") (pintype "passive"))
      (node (ref "VT1") (pin "2") (pinfunction "S_2") (pintype "passive"))
    )
    (net (code "99") (name "Net-(VT2-D)") (class "Default")
      (node (ref "C47") (pin "1") (pinfunction "1_1") (pintype "passive"))
      (node (ref "VD15") (pin "1") (pinfunction "1_1") (pintype "passive"))
      (node (ref "VD15") (pin "3") (pinfunction "3_3") (pintype "passive"))
      (node (ref "VT2") (pin "3") (pinfunction "D_3") (pintype "passive"))
      (node (ref "X11") (pin "2") (pinfunction "2_2") (pintype "passive"))
    )
    (net (code "100") (name "Net-(VT2-G)") (class "Default")
      (node (ref "R58") (pin "2") (pinfunction "2_2") (pintype "passive"))
      (node (ref "VD16") (pin "1") (pinfunction "1_1") (pintype "passive"))
      (node (ref "VT2") (pin "1") (pinfunction "G_1") (pintype "passive"))
    )
    (net (code "101") (name "PGND") (class "Default")
      (node (ref "C10") (pin "2") (pinfunction "2_2") (pintype "passive"))
      (node (ref "C11") (pin "1") (pinfunction "1_1") (pintype "passive"))
      (node (ref "C12") (pin "1") (pinfunction "1_1") (pintype "passive"))
      (node (ref "C3") (pin "1") (pinfunction "1_1") (pintype "passive"))
      (node (ref "C4") (pin "1") (pinfunction "1_1") (pintype "passive"))
      (node (ref "C5") (pin "2") (pinfunction "2_2") (pintype "passive"))
      (node (ref "C7") (pin "1") (pinfunction "1_1") (pintype "passive"))
      (node (ref "C8") (pin "1") (pinfunction "1_1") (pintype "passive"))
      (node (ref "DA3") (pin "3") (pinfunction "3_3") (pintype "passive"))
      (node (ref "DD1") (pin "2") (pinfunction "GND_2") (pintype "passive"))
      (node (ref "R23") (pin "2") (pinfunction "2_2") (pintype "passive"))
      (node (ref "R24") (pin "2") (pinfunction "2_2") (pintype "passive"))
      (node (ref "R26") (pin "1") (pinfunction "1_1") (pintype "passive"))
      (node (ref "R29") (pin "1") (pinfunction "1_1") (pintype "passive"))
      (node (ref "T1") (pin "5") (pinfunction "5_5") (pintype "passive"))
      (node (ref "VD1") (pin "2") (pinfunction "2_2") (pintype "passive"))
      (node (ref "VD4") (pin "1") (pinfunction "1_1") (pintype "passive"))
    )
    (net (code "102") (name "RIGHT_BUTTON") (class "Default")
      (node (ref "C39") (pin "1") (pinfunction "1_1") (pintype "passive"))
      (node (ref "DD2") (pin "18") (pinfunction "PB0_18") (pintype "passive"))
      (node (ref "R52") (pin "2") (pinfunction "2_2") (pintype "passive"))
      (node (ref "R53") (pin "1") (pinfunction "1_1") (pintype "passive"))
    )
    (net (code "103") (name "RIGHT_BUTTON_C") (class "Default")
      (node (ref "R53") (pin "2") (pinfunction "2_2") (pintype "passive"))
      (node (ref "X9") (pin "13") (pinfunction "13_13") (pintype "passive"))
    )
    (net (code "104") (name "SENSE_TEMP_1") (class "Default")
      (node (ref "C33") (pin "2") (pinfunction "2_2") (pintype "passive"))
      (node (ref "DD2") (pin "11") (pinfunction "PA1_11") (pintype "passive"))
      (node (ref "R42") (pin "1") (pinfunction "1_1") (pintype "passive"))
      (node (ref "VD10") (pin "2") (pinfunction "2_2") (pintype "passive"))
      (node (ref "X7") (pin "1") (pinfunction "1_1") (pintype "passive"))
    )
    (net (code "105") (name "SENSE_TEMP_2") (class "Default")
      (node (ref "C34") (pin "2") (pinfunction "2_2") (pintype "passive"))
      (node (ref "DD2") (pin "10") (pinfunction "PA0-WKUP_10") (pintype "passive"))
      (node (ref "R43") (pin "1") (pinfunction "1_1") (pintype "passive"))
      (node (ref "VD11") (pin "2") (pinfunction "2_2") (pintype "passive"))
      (node (ref "X8") (pin "1") (pinfunction "1_1") (pintype "passive"))
    )
    (net (code "106") (name "SENSE_TEMP_RADIATOR") (class "Default")
      (node (ref "C46") (pin "2") (pinfunction "2_2") (pintype "passive"))
      (node (ref "DD2") (pin "12") (pinfunction "PA2_12") (pintype "passive"))
      (node (ref "R54") (pin "2") (pinfunction "2_2") (pintype "passive"))
      (node (ref "RT1") (pin "1") (pinfunction "1_1") (pintype "passive"))
    )
    (net (code "107") (name "START_BUTTON") (class "Default")
      (node (ref "C35") (pin "1") (pinfunction "1_1") (pintype "passive"))
      (node (ref "DD2") (pin "14") (pinfunction "PA4_14") (pintype "passive"))
      (node (ref "R44") (pin "2") (pinfunction "2_2") (pintype "passive"))
      (node (ref "R45") (pin "1") (pinfunction "1_1") (pintype "passive"))
    )
    (net (code "108") (name "START_BUTTON_C") (class "Default")
      (node (ref "R45") (pin "2") (pinfunction "2_2") (pintype "passive"))
      (node (ref "X9") (pin "9") (pinfunction "9_9") (pintype "passive"))
    )
    (net (code "109") (name "STOP_BUTTON") (class "Default")
      (node (ref "C36") (pin "1") (pinfunction "1_1") (pintype "passive"))
      (node (ref "DD2") (pin "15") (pinfunction "PA5_15") (pintype "passive"))
      (node (ref "R46") (pin "2") (pinfunction "2_2") (pintype "passive"))
      (node (ref "R47") (pin "1") (pinfunction "1_1") (pintype "passive"))
    )
    (net (code "110") (name "STOP_BUTTON_C") (class "Default")
      (node (ref "R47") (pin "2") (pinfunction "2_2") (pintype "passive"))
      (node (ref "X9") (pin "10") (pinfunction "10_10") (pintype "passive"))
    )
    (net (code "111") (name "SWDCLK") (class "Default")
      (node (ref "DD2") (pin "37") (pinfunction "PA14_37") (pintype "passive"))
      (node (ref "R37") (pin "2") (pinfunction "2_2") (pintype "passive"))
    )
    (net (code "112") (name "SWDIO") (class "Default")
      (node (ref "DD2") (pin "34") (pinfunction "PA13_34") (pintype "passive"))
      (node (ref "R36") (pin "2") (pinfunction "2_2") (pintype "passive"))
      (node (ref "X9") (pin "27") (pinfunction "27_27") (pintype "passive"))
    )
    (net (code "113") (name "Speaker") (class "Default")
      (node (ref "DD2") (pin "38") (pinfunction "PA15_38") (pintype "passive"))
      (node (ref "X9") (pin "30") (pinfunction "30_30") (pintype "passive"))
    )
    (net (code "114") (name "WATER_LEVEL_HIGH") (class "Default")
      (node (ref "C31") (pin "2") (pinfunction "2_2") (pintype "passive"))
      (node (ref "DD2") (pin "13") (pinfunction "PA3_13") (pintype "passive"))
      (node (ref "R38") (pin "1") (pinfunction "1_1") (pintype "passive"))
      (node (ref "R40") (pin "1") (pinfunction "1_1") (pintype "passive"))
      (node (ref "VD8") (pin "2") (pinfunction "2_2") (pintype "passive"))
    )
    (net (code "115") (name "WATER_LEVEL_LOW") (class "Default")
      (node (ref "C32") (pin "2") (pinfunction "2_2") (pintype "passive"))
      (node (ref "DD2") (pin "2") (pinfunction "PC13-TAMPER-RTC_2") (pintype "passive"))
      (node (ref "R39") (pin "1") (pinfunction "1_1") (pintype "passive"))
      (node (ref "R41") (pin "1") (pinfunction "1_1") (pintype "passive"))
      (node (ref "VD9") (pin "2") (pinfunction "2_2") (pintype "passive"))
    )
    (net (code "116") (name "unconnected-(DA1-NC-Pad3)") (class "Default")
      (node (ref "DA1") (pin "3") (pinfunction "NC_3") (pintype "passive+no_connect"))
    )
    (net (code "117") (name "unconnected-(DA1-NC-Pad5)") (class "Default")
      (node (ref "DA1") (pin "5") (pinfunction "NC_5") (pintype "passive+no_connect"))
    )
    (net (code "118") (name "unconnected-(DA2-NC-Pad3)") (class "Default")
      (node (ref "DA2") (pin "3") (pinfunction "NC_3") (pintype "passive+no_connect"))
    )
    (net (code "119") (name "unconnected-(DA2-NC-Pad5)") (class "Default")
      (node (ref "DA2") (pin "5") (pinfunction "NC_5") (pintype "passive+no_connect"))
    )
    (net (code "120") (name "unconnected-(G1-PadG)") (class "Default")
      (node (ref "G1") (pin "G") (pinfunction "G_G") (pintype "passive+no_connect"))
    )
    (net (code "121") (name "unconnected-(G2-PadG)") (class "Default")
      (node (ref "G2") (pin "G") (pinfunction "G_G") (pintype "passive+no_connect"))
    )
    (net (code "122") (name "unconnected-(G3-PadG)") (class "Default")
      (node (ref "G3") (pin "G") (pinfunction "G_G") (pintype "passive+no_connect"))
    )
    (net (code "123") (name "unconnected-(G4-PadG)") (class "Default")
      (node (ref "G4") (pin "G") (pinfunction "G_G") (pintype "passive+no_connect"))
    )
    (net (code "124") (name "unconnected-(T1-Pad10)") (class "Default")
      (node (ref "T1") (pin "10") (pinfunction "10_10") (pintype "passive+no_connect"))
    )
    (net (code "125") (name "unconnected-(U3-NC-Pad4)") (class "Default")
      (node (ref "U3") (pin "4") (pinfunction "NC_4") (pintype "passive"))
    )
    (net (code "126") (name "unconnected-(X10-Pad3)") (class "Default")
      (node (ref "X10") (pin "3") (pinfunction "3_3") (pintype "passive"))
    )
  )
)
